# ffb_wheel.net
KiCad netlist of a schematic drawn in Altium Designer
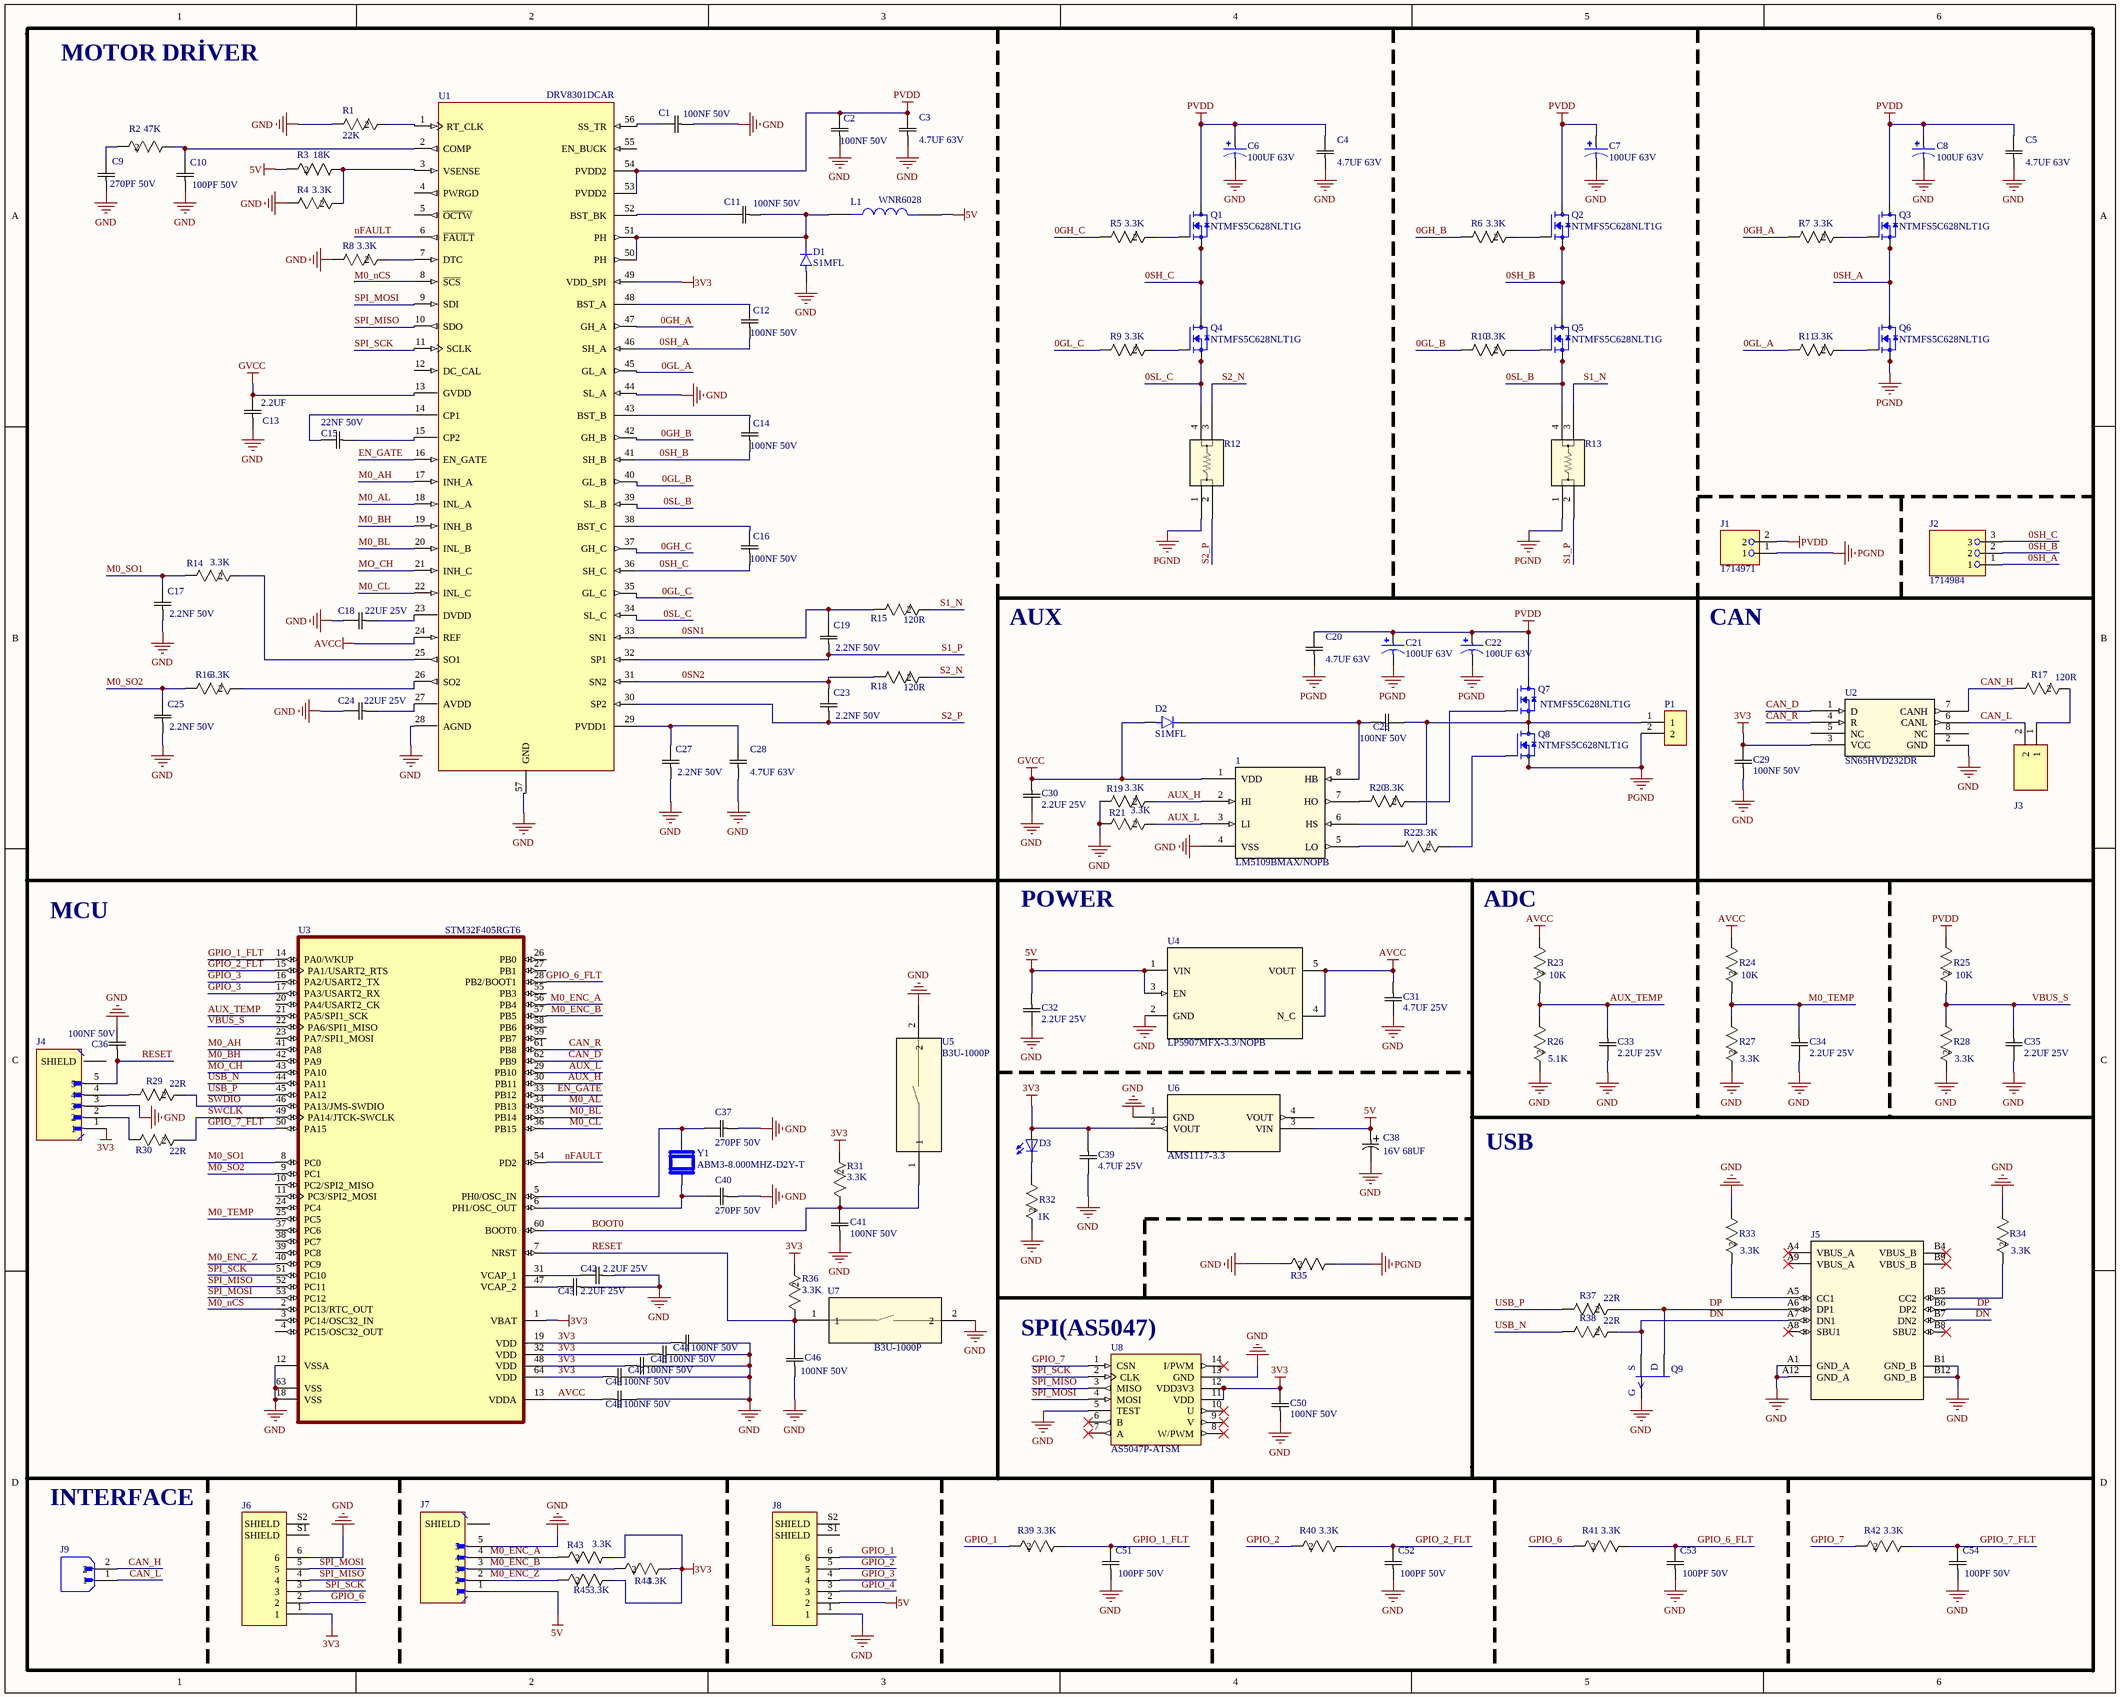
[diagram p0: ffb_wheel.SchDoc]

(export (version "E")
  (design (tool "Eeschema 10.0.6"))
  (components
    (comp (ref "1")
      (value "LM5109BMAX/NOPB")
      (footprint "M08A")
      (description "1-A, 100-V half bridge gate driver with 8-V UVLO and high noise immunity 8-SOIC -40 to 125")
      (fields (field (name "COPYRIGHT") "Copyright (C) 2025 Ultra Librarian. All rights reserved."))
      (libsource (lib "ffb_wheel") (part "LM5109BMAXNOPB"))
    )
    (comp (ref "C1")
      (value "100NF 50V")
      (footprint "CAP_0402_TDK")
      (description "No Description Available")
      (fields
        (field (name "MANUFACTURER_PART_NUMBER") "C0402X5R0J103K020BC")
        (field (name "COPYRIGHT") "Copyright (C) 2025 Ultra Librarian. All rights reserved.")
      )
      (libsource (lib "capacitor") (part "0402"))
    )
    (comp (ref "C2")
      (value "100NF 50V")
      (footprint "0603_AVX")
      (description "Description")
      (fields
        (field (name "MANUFACTURER_PART_NUMBER") "0603YC683KAT2A")
        (field (name "COPYRIGHT") "Copyright (C) 2025 Ultra Librarian. All rights reserved.")
      )
      (libsource (lib "capacitor") (part "0603"))
    )
    (comp (ref "C3")
      (value "4.7UF 63V")
      (footprint "CAP_1206_B_WAL")
      (description "Description")
      (fields
        (field (name "MANUFACTURER_PART_NUMBER") "1206B104J500CT")
        (field (name "COPYRIGHT") "Copyright (C) 2025 Ultra Librarian. All rights reserved.")
      )
      (libsource (lib "capacitor") (part "1206"))
    )
    (comp (ref "C4")
      (value "4.7UF 63V")
      (footprint "CAP_1206_B_WAL")
      (description "Description")
      (fields
        (field (name "MANUFACTURER_PART_NUMBER") "1206B104J500CT")
        (field (name "COPYRIGHT") "Copyright (C) 2025 Ultra Librarian. All rights reserved.")
      )
      (libsource (lib "capacitor") (part "1206"))
    )
    (comp (ref "C5")
      (value "4.7UF 63V")
      (footprint "CAP_1206_B_WAL")
      (description "Description")
      (fields
        (field (name "MANUFACTURER_PART_NUMBER") "1206B104J500CT")
        (field (name "COPYRIGHT") "Copyright (C) 2025 Ultra Librarian. All rights reserved.")
      )
      (libsource (lib "capacitor") (part "1206"))
    )
    (comp (ref "C6")
      (value "100UF 63V")
      (footprint "CAP_EEEFT1C102GP")
      (description "Cap Aluminum 1000uF 16V 20% (10 X 10.2mm) SMD Cylindrical 0.06 Ohm 1190mA 5000hr 105Â°C Emboss T/R")
      (fields (field (name "DIGI-KEY_PART_NUMBER") "PCE5115TR-ND") (field (name "MF") "Panasonic"))
      (libsource (lib "ffb_wheel") (part "EEEFT1C102GP"))
    )
    (comp (ref "C7")
      (value "100UF 63V")
      (footprint "CAP_EEEFT1C102GP")
      (description "Cap Aluminum 1000uF 16V 20% (10 X 10.2mm) SMD Cylindrical 0.06 Ohm 1190mA 5000hr 105Â°C Emboss T/R")
      (fields (field (name "DIGI-KEY_PART_NUMBER") "PCE5115TR-ND") (field (name "MF") "Panasonic"))
      (libsource (lib "ffb_wheel") (part "EEEFT1C102GP"))
    )
    (comp (ref "C8")
      (value "100UF 63V")
      (footprint "CAP_EEEFT1C102GP")
      (description "Cap Aluminum 1000uF 16V 20% (10 X 10.2mm) SMD Cylindrical 0.06 Ohm 1190mA 5000hr 105Â°C Emboss T/R")
      (fields (field (name "DIGI-KEY_PART_NUMBER") "PCE5115TR-ND") (field (name "MF") "Panasonic"))
      (libsource (lib "ffb_wheel") (part "EEEFT1C102GP"))
    )
    (comp (ref "C9")
      (value "270PF 50V")
      (footprint "CAP_0402_TDK")
      (description "No Description Available")
      (fields
        (field (name "MANUFACTURER_PART_NUMBER") "C0402X5R0J103K020BC")
        (field (name "COPYRIGHT") "Copyright (C) 2025 Ultra Librarian. All rights reserved.")
      )
      (libsource (lib "capacitor") (part "0402"))
    )
    (comp (ref "C10")
      (value "100PF 50V")
      (footprint "CAP_0402_TDK")
      (description "No Description Available")
      (fields
        (field (name "MANUFACTURER_PART_NUMBER") "C0402X5R0J103K020BC")
        (field (name "COPYRIGHT") "Copyright (C) 2025 Ultra Librarian. All rights reserved.")
      )
      (libsource (lib "capacitor") (part "0402"))
    )
    (comp (ref "C11")
      (value "100NF 50V")
      (footprint "0603_AVX")
      (description "Description")
      (fields
        (field (name "MANUFACTURER_PART_NUMBER") "0603YC683KAT2A")
        (field (name "COPYRIGHT") "Copyright (C) 2025 Ultra Librarian. All rights reserved.")
      )
      (libsource (lib "capacitor") (part "0603"))
    )
    (comp (ref "C12")
      (value "100NF 50V")
      (footprint "0603_AVX")
      (description "Description")
      (fields
        (field (name "MANUFACTURER_PART_NUMBER") "0603YC683KAT2A")
        (field (name "COPYRIGHT") "Copyright (C) 2025 Ultra Librarian. All rights reserved.")
      )
      (libsource (lib "capacitor") (part "0603"))
    )
    (comp (ref "C13")
      (value "2.2UF")
      (footprint "0805_AVX")
      (description "Description")
      (fields
        (field (name "MANUFACTURER_PART_NUMBER") "08051C473KAT2A")
        (field (name "COPYRIGHT") "Copyright (C) 2025 Ultra Librarian. All rights reserved.")
      )
      (libsource (lib "capacitor") (part "0805"))
    )
    (comp (ref "C14")
      (value "100NF 50V")
      (footprint "0603_AVX")
      (description "Description")
      (fields
        (field (name "MANUFACTURER_PART_NUMBER") "0603YC683KAT2A")
        (field (name "COPYRIGHT") "Copyright (C) 2025 Ultra Librarian. All rights reserved.")
      )
      (libsource (lib "capacitor") (part "0603"))
    )
    (comp (ref "C15")
      (value "22NF 50V")
      (footprint "CAP_0402_TDK")
      (description "No Description Available")
      (fields
        (field (name "MANUFACTURER_PART_NUMBER") "C0402X5R0J103K020BC")
        (field (name "COPYRIGHT") "Copyright (C) 2025 Ultra Librarian. All rights reserved.")
      )
      (libsource (lib "capacitor") (part "0402"))
    )
    (comp (ref "C16")
      (value "100NF 50V")
      (footprint "0603_AVX")
      (description "Description")
      (fields
        (field (name "MANUFACTURER_PART_NUMBER") "0603YC683KAT2A")
        (field (name "COPYRIGHT") "Copyright (C) 2025 Ultra Librarian. All rights reserved.")
      )
      (libsource (lib "capacitor") (part "0603"))
    )
    (comp (ref "C17")
      (value "2.2NF 50V")
      (footprint "CAP_0402_TDK")
      (description "No Description Available")
      (fields
        (field (name "MANUFACTURER_PART_NUMBER") "C0402X5R0J103K020BC")
        (field (name "COPYRIGHT") "Copyright (C) 2025 Ultra Librarian. All rights reserved.")
      )
      (libsource (lib "capacitor") (part "0402"))
    )
    (comp (ref "C18")
      (value "22UF 25V")
      (footprint "0805_AVX")
      (description "Description")
      (fields
        (field (name "MANUFACTURER_PART_NUMBER") "08051C473KAT2A")
        (field (name "COPYRIGHT") "Copyright (C) 2025 Ultra Librarian. All rights reserved.")
      )
      (libsource (lib "capacitor") (part "0805"))
    )
    (comp (ref "C19")
      (value "2.2NF 50V")
      (footprint "CAP_0402_TDK")
      (description "No Description Available")
      (fields
        (field (name "MANUFACTURER_PART_NUMBER") "C0402X5R0J103K020BC")
        (field (name "COPYRIGHT") "Copyright (C) 2025 Ultra Librarian. All rights reserved.")
      )
      (libsource (lib "capacitor") (part "0402"))
    )
    (comp (ref "C20")
      (value "4.7UF 63V")
      (footprint "CAP_1206_B_WAL")
      (description "Description")
      (fields
        (field (name "MANUFACTURER_PART_NUMBER") "1206B104J500CT")
        (field (name "COPYRIGHT") "Copyright (C) 2025 Ultra Librarian. All rights reserved.")
      )
      (libsource (lib "capacitor") (part "1206"))
    )
    (comp (ref "C21")
      (value "100UF 63V")
      (footprint "CAP_EEEFT1C102GP")
      (description "Cap Aluminum 1000uF 16V 20% (10 X 10.2mm) SMD Cylindrical 0.06 Ohm 1190mA 5000hr 105Â°C Emboss T/R")
      (fields (field (name "DIGI-KEY_PART_NUMBER") "PCE5115TR-ND") (field (name "MF") "Panasonic"))
      (libsource (lib "ffb_wheel") (part "EEEFT1C102GP"))
    )
    (comp (ref "C22")
      (value "100UF 63V")
      (footprint "CAP_EEEFT1C102GP")
      (description "Cap Aluminum 1000uF 16V 20% (10 X 10.2mm) SMD Cylindrical 0.06 Ohm 1190mA 5000hr 105Â°C Emboss T/R")
      (fields (field (name "DIGI-KEY_PART_NUMBER") "PCE5115TR-ND") (field (name "MF") "Panasonic"))
      (libsource (lib "ffb_wheel") (part "EEEFT1C102GP"))
    )
    (comp (ref "C23")
      (value "2.2NF 50V")
      (footprint "CAP_0402_TDK")
      (description "No Description Available")
      (fields
        (field (name "MANUFACTURER_PART_NUMBER") "C0402X5R0J103K020BC")
        (field (name "COPYRIGHT") "Copyright (C) 2025 Ultra Librarian. All rights reserved.")
      )
      (libsource (lib "capacitor") (part "0402"))
    )
    (comp (ref "C24")
      (value "22UF 25V")
      (footprint "0805_AVX")
      (description "Description")
      (fields
        (field (name "MANUFACTURER_PART_NUMBER") "08051C473KAT2A")
        (field (name "COPYRIGHT") "Copyright (C) 2025 Ultra Librarian. All rights reserved.")
      )
      (libsource (lib "capacitor") (part "0805"))
    )
    (comp (ref "C25")
      (value "2.2NF 50V")
      (footprint "CAP_0402_TDK")
      (description "No Description Available")
      (fields
        (field (name "MANUFACTURER_PART_NUMBER") "C0402X5R0J103K020BC")
        (field (name "COPYRIGHT") "Copyright (C) 2025 Ultra Librarian. All rights reserved.")
      )
      (libsource (lib "capacitor") (part "0402"))
    )
    (comp (ref "C26")
      (value "100NF 50V")
      (footprint "0603_AVX")
      (description "Description")
      (fields
        (field (name "MANUFACTURER_PART_NUMBER") "0603YC683KAT2A")
        (field (name "COPYRIGHT") "Copyright (C) 2025 Ultra Librarian. All rights reserved.")
      )
      (libsource (lib "capacitor") (part "0603"))
    )
    (comp (ref "C27")
      (value "2.2NF 50V")
      (footprint "CAP_0402_TDK")
      (description "No Description Available")
      (fields
        (field (name "MANUFACTURER_PART_NUMBER") "C0402X5R0J103K020BC")
        (field (name "COPYRIGHT") "Copyright (C) 2025 Ultra Librarian. All rights reserved.")
      )
      (libsource (lib "capacitor") (part "0402"))
    )
    (comp (ref "C28")
      (value "4.7UF 63V")
      (footprint "CAP_1206_B_WAL")
      (description "Description")
      (fields
        (field (name "MANUFACTURER_PART_NUMBER") "1206B104J500CT")
        (field (name "COPYRIGHT") "Copyright (C) 2025 Ultra Librarian. All rights reserved.")
      )
      (libsource (lib "capacitor") (part "1206"))
    )
    (comp (ref "C29")
      (value "100NF 50V")
      (footprint "0603_AVX")
      (description "Description")
      (fields
        (field (name "MANUFACTURER_PART_NUMBER") "0603YC683KAT2A")
        (field (name "COPYRIGHT") "Copyright (C) 2025 Ultra Librarian. All rights reserved.")
      )
      (libsource (lib "capacitor") (part "0603"))
    )
    (comp (ref "C30")
      (value "2.2UF 25V")
      (footprint "0805_AVX")
      (description "Description")
      (fields
        (field (name "MANUFACTURER_PART_NUMBER") "08051C473KAT2A")
        (field (name "COPYRIGHT") "Copyright (C) 2025 Ultra Librarian. All rights reserved.")
      )
      (libsource (lib "capacitor") (part "0805"))
    )
    (comp (ref "C31")
      (value "4.7UF 25V")
      (footprint "0805_AVX")
      (description "Description")
      (fields
        (field (name "MANUFACTURER_PART_NUMBER") "08051C473KAT2A")
        (field (name "COPYRIGHT") "Copyright (C) 2025 Ultra Librarian. All rights reserved.")
      )
      (libsource (lib "capacitor") (part "0805"))
    )
    (comp (ref "C32")
      (value "2.2UF 25V")
      (footprint "0805_AVX")
      (description "Description")
      (fields
        (field (name "MANUFACTURER_PART_NUMBER") "08051C473KAT2A")
        (field (name "COPYRIGHT") "Copyright (C) 2025 Ultra Librarian. All rights reserved.")
      )
      (libsource (lib "capacitor") (part "0805"))
    )
    (comp (ref "C33")
      (value "2.2UF 25V")
      (footprint "0805_AVX")
      (description "Description")
      (fields
        (field (name "MANUFACTURER_PART_NUMBER") "08051C473KAT2A")
        (field (name "COPYRIGHT") "Copyright (C) 2025 Ultra Librarian. All rights reserved.")
      )
      (libsource (lib "capacitor") (part "0805"))
    )
    (comp (ref "C34")
      (value "2.2UF 25V")
      (footprint "0805_AVX")
      (description "Description")
      (fields
        (field (name "MANUFACTURER_PART_NUMBER") "08051C473KAT2A")
        (field (name "COPYRIGHT") "Copyright (C) 2025 Ultra Librarian. All rights reserved.")
      )
      (libsource (lib "capacitor") (part "0805"))
    )
    (comp (ref "C35")
      (value "2.2UF 25V")
      (footprint "0805_AVX")
      (description "Description")
      (fields
        (field (name "MANUFACTURER_PART_NUMBER") "08051C473KAT2A")
        (field (name "COPYRIGHT") "Copyright (C) 2025 Ultra Librarian. All rights reserved.")
      )
      (libsource (lib "capacitor") (part "0805"))
    )
    (comp (ref "C36")
      (value "100NF 50V")
      (footprint "0603_AVX")
      (description "Description")
      (fields
        (field (name "MANUFACTURER_PART_NUMBER") "0603YC683KAT2A")
        (field (name "COPYRIGHT") "Copyright (C) 2025 Ultra Librarian. All rights reserved.")
      )
      (libsource (lib "capacitor") (part "0603"))
    )
    (comp (ref "C37")
      (value "270PF 50V")
      (footprint "CAP_0402_TDK")
      (description "No Description Available")
      (fields
        (field (name "MANUFACTURER_PART_NUMBER") "C0402X5R0J103K020BC")
        (field (name "COPYRIGHT") "Copyright (C) 2025 Ultra Librarian. All rights reserved.")
      )
      (libsource (lib "capacitor") (part "0402"))
    )
    (comp (ref "C38")
      (value "16V 68UF")
      (footprint "TAJB_AVX")
      (description "Cap Tant Solid 47uF 6.3V B CASE 10% (3.5 X 2.8 X 1.9mm)")
      (fields
        (field (name "MANUFACTURER_PART_NUMBER") "TAJB476K006RNJ")
        (field (name "COPYRIGHT") "Copyright (C) 2025 Ultra Librarian. All rights reserved.")
      )
      (libsource (lib "capacitor") (part "(3.5 X 2.8 X 1.9mm)"))
    )
    (comp (ref "C39")
      (value "4.7UF 25V")
      (footprint "0805_AVX")
      (description "Description")
      (fields
        (field (name "MANUFACTURER_PART_NUMBER") "08051C473KAT2A")
        (field (name "COPYRIGHT") "Copyright (C) 2025 Ultra Librarian. All rights reserved.")
      )
      (libsource (lib "capacitor") (part "0805"))
    )
    (comp (ref "C40")
      (value "270PF 50V")
      (footprint "CAP_0402_TDK")
      (description "No Description Available")
      (fields
        (field (name "MANUFACTURER_PART_NUMBER") "C0402X5R0J103K020BC")
        (field (name "COPYRIGHT") "Copyright (C) 2025 Ultra Librarian. All rights reserved.")
      )
      (libsource (lib "capacitor") (part "0402"))
    )
    (comp (ref "C41")
      (value "100NF 50V")
      (footprint "0603_AVX")
      (description "Description")
      (fields
        (field (name "MANUFACTURER_PART_NUMBER") "0603YC683KAT2A")
        (field (name "COPYRIGHT") "Copyright (C) 2025 Ultra Librarian. All rights reserved.")
      )
      (libsource (lib "capacitor") (part "0603"))
    )
    (comp (ref "C42")
      (value "2.2UF 25V")
      (footprint "0805_AVX")
      (description "Description")
      (fields
        (field (name "MANUFACTURER_PART_NUMBER") "08051C473KAT2A")
        (field (name "COPYRIGHT") "Copyright (C) 2025 Ultra Librarian. All rights reserved.")
      )
      (libsource (lib "capacitor") (part "0805"))
    )
    (comp (ref "C43")
      (value "2.2UF 25V")
      (footprint "0805_AVX")
      (description "Description")
      (fields
        (field (name "MANUFACTURER_PART_NUMBER") "08051C473KAT2A")
        (field (name "COPYRIGHT") "Copyright (C) 2025 Ultra Librarian. All rights reserved.")
      )
      (libsource (lib "capacitor") (part "0805"))
    )
    (comp (ref "C44")
      (value "100NF 50V")
      (footprint "0603_AVX")
      (description "Description")
      (fields
        (field (name "MANUFACTURER_PART_NUMBER") "0603YC683KAT2A")
        (field (name "COPYRIGHT") "Copyright (C) 2025 Ultra Librarian. All rights reserved.")
      )
      (libsource (lib "capacitor") (part "0603"))
    )
    (comp (ref "C45")
      (value "100NF 50V")
      (footprint "0603_AVX")
      (description "Description")
      (fields
        (field (name "MANUFACTURER_PART_NUMBER") "0603YC683KAT2A")
        (field (name "COPYRIGHT") "Copyright (C) 2025 Ultra Librarian. All rights reserved.")
      )
      (libsource (lib "capacitor") (part "0603"))
    )
    (comp (ref "C46")
      (value "100NF 50V")
      (footprint "0603_AVX")
      (description "Description")
      (fields
        (field (name "MANUFACTURER_PART_NUMBER") "0603YC683KAT2A")
        (field (name "COPYRIGHT") "Copyright (C) 2025 Ultra Librarian. All rights reserved.")
      )
      (libsource (lib "capacitor") (part "0603"))
    )
    (comp (ref "C47")
      (value "100NF 50V")
      (footprint "0603_AVX")
      (description "Description")
      (fields
        (field (name "MANUFACTURER_PART_NUMBER") "0603YC683KAT2A")
        (field (name "COPYRIGHT") "Copyright (C) 2025 Ultra Librarian. All rights reserved.")
      )
      (libsource (lib "capacitor") (part "0603"))
    )
    (comp (ref "C48")
      (value "100NF 50V")
      (footprint "0603_AVX")
      (description "Description")
      (fields
        (field (name "MANUFACTURER_PART_NUMBER") "0603YC683KAT2A")
        (field (name "COPYRIGHT") "Copyright (C) 2025 Ultra Librarian. All rights reserved.")
      )
      (libsource (lib "capacitor") (part "0603"))
    )
    (comp (ref "C49")
      (value "100NF 50V")
      (footprint "0603_AVX")
      (description "Description")
      (fields
        (field (name "MANUFACTURER_PART_NUMBER") "0603YC683KAT2A")
        (field (name "COPYRIGHT") "Copyright (C) 2025 Ultra Librarian. All rights reserved.")
      )
      (libsource (lib "capacitor") (part "0603"))
    )
    (comp (ref "C50")
      (value "100NF 50V")
      (footprint "0603_AVX")
      (description "Description")
      (fields
        (field (name "MANUFACTURER_PART_NUMBER") "0603YC683KAT2A")
        (field (name "COPYRIGHT") "Copyright (C) 2025 Ultra Librarian. All rights reserved.")
      )
      (libsource (lib "capacitor") (part "0603"))
    )
    (comp (ref "C51")
      (value "100PF 50V")
      (footprint "CAP_0402_TDK")
      (description "No Description Available")
      (fields
        (field (name "MANUFACTURER_PART_NUMBER") "C0402X5R0J103K020BC")
        (field (name "COPYRIGHT") "Copyright (C) 2025 Ultra Librarian. All rights reserved.")
      )
      (libsource (lib "capacitor") (part "0402"))
    )
    (comp (ref "C52")
      (value "100PF 50V")
      (footprint "CAP_0402_TDK")
      (description "No Description Available")
      (fields
        (field (name "MANUFACTURER_PART_NUMBER") "C0402X5R0J103K020BC")
        (field (name "COPYRIGHT") "Copyright (C) 2025 Ultra Librarian. All rights reserved.")
      )
      (libsource (lib "capacitor") (part "0402"))
    )
    (comp (ref "C53")
      (value "100PF 50V")
      (footprint "CAP_0402_TDK")
      (description "No Description Available")
      (fields
        (field (name "MANUFACTURER_PART_NUMBER") "C0402X5R0J103K020BC")
        (field (name "COPYRIGHT") "Copyright (C) 2025 Ultra Librarian. All rights reserved.")
      )
      (libsource (lib "capacitor") (part "0402"))
    )
    (comp (ref "C54")
      (value "100PF 50V")
      (footprint "CAP_0402_TDK")
      (description "No Description Available")
      (fields
        (field (name "MANUFACTURER_PART_NUMBER") "C0402X5R0J103K020BC")
        (field (name "COPYRIGHT") "Copyright (C) 2025 Ultra Librarian. All rights reserved.")
      )
      (libsource (lib "capacitor") (part "0402"))
    )
    (comp (ref "D1")
      (value "S1MFL")
      (footprint "SODFL3617X108N")
      (description "Diode Standard 1000 V 1A Surface Mount SOD-123F")
      (fields (field (name "MF") "ON Semiconductor"))
      (libsource (lib "ffb_wheel") (part "S1MFL"))
    )
    (comp (ref "D2")
      (value "S1MFL")
      (footprint "SODFL3617X108N")
      (description "Diode Standard 1000 V 1A Surface Mount SOD-123F")
      (fields (field (name "MF") "ON Semiconductor"))
      (libsource (lib "ffb_wheel") (part "S1MFL"))
    )
    (comp (ref "D3")
      (value "LTST-C170TBKT")
      (footprint "DIOC200X125X110")
      (description "Blue 470nm LED Indication - Discrete 3.3V 0805 (2012 Metric)")
      (fields (field (name "MF") "Lite-On Electronics"))
      (libsource (lib "batterie") (part "LTST-C170TBKT"))
    )
    (comp (ref "J1")
      (value "1714971")
      (footprint "PHOENIX_1714971")
      (libsource (lib "ffb_wheel") (part "1714971"))
    )
    (comp (ref "J2")
      (value "1714984")
      (footprint "PHOENIX_1714984")
      (fields (field (name "MF") "Phoenix Contact"))
      (libsource (lib "ffb_wheel") (part "1714984"))
    )
    (comp (ref "J3")
      (value "3-644456-2")
      (footprint "TE_3-644456-2")
      (description "HEADER ASSEMBLY, NARROW, MTA-100, 2 POSITION, STRAIGHT ¦ TE Connectivity 3-644456-2")
      (fields (field (name "MF") "TE Connectivity"))
      (libsource (lib "ffb_wheel") (part "3-644456-2"))
    )
    (comp (ref "J4")
      (value "BM05B-GHS-TBT(LF)(SN)(N)")
      (footprint "JST_BM05B-GHS-TBT(LF)(SN)(N)")
      (description "Connector Header Surface Mount 5 position 0.049 (1.25mm)")
      (fields (field (name "MF") "JST Sales"))
      (libsource (lib "ffb_wheel") (part "BM05B-GHS-TBT(LF)(SN)(N)"))
    )
    (comp (ref "J5")
      (value "USB4145-03-0230-C")
      (footprint "CONN_USB4145-03-0230-C_GCT")
      (description "Description")
      (fields (field (name "COPYRIGHT") "Copyright (C) 2025 Ultra Librarian. All rights reserved."))
      (libsource (lib "ffb_wheel") (part "USB4145-03-0230-C"))
    )
    (comp (ref "J6")
      (value "BM06B-GHS-TBT(LF)(SN)(N)")
      (footprint "JST_BM06B-GHS-TBT(LF)(SN)(N)")
      (description "Connector Header Surface Mount 6 position 0.049 (1.25mm)")
      (fields (field (name "MF") "JST Sales"))
      (libsource (lib "ffb_wheel") (part "BM06B-GHS-TBT(LF)(SN)(N)"))
    )
    (comp (ref "J7")
      (value "BM05B-GHS-TBT(LF)(SN)(N)")
      (footprint "JST_BM05B-GHS-TBT(LF)(SN)(N)")
      (description "Connector Header Surface Mount 5 position 0.049 (1.25mm)")
      (fields (field (name "MF") "JST Sales"))
      (libsource (lib "ffb_wheel") (part "BM05B-GHS-TBT(LF)(SN)(N)"))
    )
    (comp (ref "J8")
      (value "BM06B-GHS-TBT(LF)(SN)(N)")
      (footprint "JST_BM06B-GHS-TBT(LF)(SN)(N)")
      (description "Connector Header Surface Mount 6 position 0.049 (1.25mm)")
      (fields (field (name "MF") "JST Sales"))
      (libsource (lib "ffb_wheel") (part "BM06B-GHS-TBT(LF)(SN)(N)"))
    )
    (comp (ref "J9")
      (value "BM02B-GHS-TBT(LF)(SN)")
      (footprint "JST_BM02B-GHS-TBT(LF)(SN)")
      (description "Connector Header Surface Mount 2 position 0.049 (1.25mm)")
      (fields (field (name "MF") "JST Sales") (field (name "MP") "BM02B-GHS-TBT (LF)(SN)"))
      (libsource (lib "ffb_wheel") (part "BM02B-GHS-TBT(LF)(SN)"))
    )
    (comp (ref "L1")
      (value "WNR6028")
      (footprint "IND_NR6028T4R7M")
      (description "4.7 ÂµH Shielded Drum Core, Wirewound Inductor 3 A 40.3mOhm Max Nonstandard")
      (fields (field (name "MF") "Taiyo Yuden") (field (name "MP") "NR6028T4R7M"))
      (libsource (lib "ffb_wheel") (part "NR6028T4R7M"))
    )
    (comp (ref "P1")
      (value "282837-2")
      (footprint "TE_282837-2")
      (fields (field (name "MF") "TE Connectivity"))
      (libsource (lib "ffb_wheel") (part "282837-2"))
    )
    (comp (ref "Q1")
      (value "NTMFS5C628NLT1G")
      (footprint "TRANS_NTMFS5C628NLT1G")
      (description "N-Channel 60 V 28A (Ta), 150A (Tc) 3.7W (Ta), 110W (Tc) Surface Mount 5-DFN (5x6) (8-SOFL)")
      (fields (field (name "MF") "ON Semiconductor"))
      (libsource (lib "ffb_wheel") (part "NTMFS5C628NLT1G"))
    )
    (comp (ref "Q2")
      (value "NTMFS5C628NLT1G")
      (footprint "TRANS_NTMFS5C628NLT1G")
      (description "N-Channel 60 V 28A (Ta), 150A (Tc) 3.7W (Ta), 110W (Tc) Surface Mount 5-DFN (5x6) (8-SOFL)")
      (fields (field (name "MF") "ON Semiconductor"))
      (libsource (lib "ffb_wheel") (part "NTMFS5C628NLT1G"))
    )
    (comp (ref "Q3")
      (value "NTMFS5C628NLT1G")
      (footprint "TRANS_NTMFS5C628NLT1G")
      (description "N-Channel 60 V 28A (Ta), 150A (Tc) 3.7W (Ta), 110W (Tc) Surface Mount 5-DFN (5x6) (8-SOFL)")
      (fields (field (name "MF") "ON Semiconductor"))
      (libsource (lib "ffb_wheel") (part "NTMFS5C628NLT1G"))
    )
    (comp (ref "Q4")
      (value "NTMFS5C628NLT1G")
      (footprint "TRANS_NTMFS5C628NLT1G")
      (description "N-Channel 60 V 28A (Ta), 150A (Tc) 3.7W (Ta), 110W (Tc) Surface Mount 5-DFN (5x6) (8-SOFL)")
      (fields (field (name "MF") "ON Semiconductor"))
      (libsource (lib "ffb_wheel") (part "NTMFS5C628NLT1G"))
    )
    (comp (ref "Q5")
      (value "NTMFS5C628NLT1G")
      (footprint "TRANS_NTMFS5C628NLT1G")
      (description "N-Channel 60 V 28A (Ta), 150A (Tc) 3.7W (Ta), 110W (Tc) Surface Mount 5-DFN (5x6) (8-SOFL)")
      (fields (field (name "MF") "ON Semiconductor"))
      (libsource (lib "ffb_wheel") (part "NTMFS5C628NLT1G"))
    )
    (comp (ref "Q6")
      (value "NTMFS5C628NLT1G")
      (footprint "TRANS_NTMFS5C628NLT1G")
      (description "N-Channel 60 V 28A (Ta), 150A (Tc) 3.7W (Ta), 110W (Tc) Surface Mount 5-DFN (5x6) (8-SOFL)")
      (fields (field (name "MF") "ON Semiconductor"))
      (libsource (lib "ffb_wheel") (part "NTMFS5C628NLT1G"))
    )
    (comp (ref "Q7")
      (value "NTMFS5C628NLT1G")
      (footprint "TRANS_NTMFS5C628NLT1G")
      (description "N-Channel 60 V 28A (Ta), 150A (Tc) 3.7W (Ta), 110W (Tc) Surface Mount 5-DFN (5x6) (8-SOFL)")
      (fields (field (name "MF") "ON Semiconductor"))
      (libsource (lib "ffb_wheel") (part "NTMFS5C628NLT1G"))
    )
    (comp (ref "Q8")
      (value "NTMFS5C628NLT1G")
      (footprint "TRANS_NTMFS5C628NLT1G")
      (description "N-Channel 60 V 28A (Ta), 150A (Tc) 3.7W (Ta), 110W (Tc) Surface Mount 5-DFN (5x6) (8-SOFL)")
      (fields (field (name "MF") "ON Semiconductor"))
      (libsource (lib "ffb_wheel") (part "NTMFS5C628NLT1G"))
    )
    (comp (ref "Q9")
      (value "SST176-SOT-23_3L")
      (footprint "SOT96P237X122-3N")
      (description "P-CHANNEL, SINGLE, JFET SWITCH")
      (fields (field (name "MF") "Linear Systems") (field (name "MP") "SST176-SOT-23 3L"))
      (libsource (lib "ffb_wheel") (part "SST176-SOT-23_3L"))
    )
    (comp (ref "R1")
      (value "22K")
      (footprint "RC0603N_PAN")
      (description "No Description Available")
      (fields
        (field (name "MANUFACTURER_PART_NUMBER") "ERJ-3GEYJ6R8V")
        (field (name "COPYRIGHT") "Copyright (C) 2025 Ultra Librarian. All rights reserved.")
      )
      (libsource (lib "resistor") (part "0603"))
    )
    (comp (ref "R2")
      (value "47K")
      (footprint "RC0603N_PAN")
      (description "No Description Available")
      (fields
        (field (name "MANUFACTURER_PART_NUMBER") "ERJ-3GEYJ6R8V")
        (field (name "COPYRIGHT") "Copyright (C) 2025 Ultra Librarian. All rights reserved.")
      )
      (libsource (lib "resistor") (part "0603"))
    )
    (comp (ref "R3")
      (value "18K")
      (footprint "RC0603N_PAN")
      (description "No Description Available")
      (fields
        (field (name "MANUFACTURER_PART_NUMBER") "ERJ-3GEYJ6R8V")
        (field (name "COPYRIGHT") "Copyright (C) 2025 Ultra Librarian. All rights reserved.")
      )
      (libsource (lib "resistor") (part "0603"))
    )
    (comp (ref "R4")
      (value "3.3K")
      (footprint "RC0603N_PAN")
      (description "No Description Available")
      (fields
        (field (name "MANUFACTURER_PART_NUMBER") "ERJ-3GEYJ6R8V")
        (field (name "COPYRIGHT") "Copyright (C) 2025 Ultra Librarian. All rights reserved.")
      )
      (libsource (lib "resistor") (part "0603"))
    )
    (comp (ref "R5")
      (value "3.3K")
      (footprint "RC0603N_PAN")
      (description "No Description Available")
      (fields
        (field (name "MANUFACTURER_PART_NUMBER") "ERJ-3GEYJ6R8V")
        (field (name "COPYRIGHT") "Copyright (C) 2025 Ultra Librarian. All rights reserved.")
      )
      (libsource (lib "resistor") (part "0603"))
    )
    (comp (ref "R6")
      (value "3.3K")
      (footprint "RC0603N_PAN")
      (description "No Description Available")
      (fields
        (field (name "MANUFACTURER_PART_NUMBER") "ERJ-3GEYJ6R8V")
        (field (name "COPYRIGHT") "Copyright (C) 2025 Ultra Librarian. All rights reserved.")
      )
      (libsource (lib "resistor") (part "0603"))
    )
    (comp (ref "R7")
      (value "3.3K")
      (footprint "RC0603N_PAN")
      (description "No Description Available")
      (fields
        (field (name "MANUFACTURER_PART_NUMBER") "ERJ-3GEYJ6R8V")
        (field (name "COPYRIGHT") "Copyright (C) 2025 Ultra Librarian. All rights reserved.")
      )
      (libsource (lib "resistor") (part "0603"))
    )
    (comp (ref "R8")
      (value "3.3K")
      (footprint "RC0603N_PAN")
      (description "No Description Available")
      (fields
        (field (name "MANUFACTURER_PART_NUMBER") "ERJ-3GEYJ6R8V")
        (field (name "COPYRIGHT") "Copyright (C) 2025 Ultra Librarian. All rights reserved.")
      )
      (libsource (lib "resistor") (part "0603"))
    )
    (comp (ref "R9")
      (value "3.3K")
      (footprint "RC0603N_PAN")
      (description "No Description Available")
      (fields
        (field (name "MANUFACTURER_PART_NUMBER") "ERJ-3GEYJ6R8V")
        (field (name "COPYRIGHT") "Copyright (C) 2025 Ultra Librarian. All rights reserved.")
      )
      (libsource (lib "resistor") (part "0603"))
    )
    (comp (ref "R10")
      (value "3.3K")
      (footprint "RC0603N_PAN")
      (description "No Description Available")
      (fields
        (field (name "MANUFACTURER_PART_NUMBER") "ERJ-3GEYJ6R8V")
        (field (name "COPYRIGHT") "Copyright (C) 2025 Ultra Librarian. All rights reserved.")
      )
      (libsource (lib "resistor") (part "0603"))
    )
    (comp (ref "R11")
      (value "3.3K")
      (footprint "RC0603N_PAN")
      (description "No Description Available")
      (fields
        (field (name "MANUFACTURER_PART_NUMBER") "ERJ-3GEYJ6R8V")
        (field (name "COPYRIGHT") "Copyright (C) 2025 Ultra Librarian. All rights reserved.")
      )
      (libsource (lib "resistor") (part "0603"))
    )
    (comp (ref "R12")
      (value "WSK2512R0100DEA")
      (footprint "WSK2512_0.005-0.2_VIS")
      (description "WSK-2512 .01 .5% EA e3")
      (fields (field (name "COPYRIGHT") "Copyright (C) 2025 Ultra Librarian. All rights reserved."))
      (libsource (lib "ffb_wheel") (part "WSK2512R0100DEA"))
    )
    (comp (ref "R13")
      (value "WSK2512R0100DEA")
      (footprint "WSK2512_0.005-0.2_VIS")
      (description "WSK-2512 .01 .5% EA e3")
      (fields (field (name "COPYRIGHT") "Copyright (C) 2025 Ultra Librarian. All rights reserved."))
      (libsource (lib "ffb_wheel") (part "WSK2512R0100DEA"))
    )
    (comp (ref "R14")
      (value "3.3K")
      (footprint "RC0603N_PAN")
      (description "No Description Available")
      (fields
        (field (name "MANUFACTURER_PART_NUMBER") "ERJ-3GEYJ6R8V")
        (field (name "COPYRIGHT") "Copyright (C) 2025 Ultra Librarian. All rights reserved.")
      )
      (libsource (lib "resistor") (part "0603"))
    )
    (comp (ref "R15")
      (value "120R")
      (footprint "RC0603N_PAN")
      (description "No Description Available")
      (fields
        (field (name "MANUFACTURER_PART_NUMBER") "ERJ-3GEYJ6R8V")
        (field (name "COPYRIGHT") "Copyright (C) 2025 Ultra Librarian. All rights reserved.")
      )
      (libsource (lib "resistor") (part "0603"))
    )
    (comp (ref "R16")
      (value "3.3K")
      (footprint "RC0603N_PAN")
      (description "No Description Available")
      (fields
        (field (name "MANUFACTURER_PART_NUMBER") "ERJ-3GEYJ6R8V")
        (field (name "COPYRIGHT") "Copyright (C) 2025 Ultra Librarian. All rights reserved.")
      )
      (libsource (lib "resistor") (part "0603"))
    )
    (comp (ref "R17")
      (value "120R")
      (footprint "RC0603N_PAN")
      (description "No Description Available")
      (fields
        (field (name "MANUFACTURER_PART_NUMBER") "ERJ-3GEYJ6R8V")
        (field (name "COPYRIGHT") "Copyright (C) 2025 Ultra Librarian. All rights reserved.")
      )
      (libsource (lib "resistor") (part "0603"))
    )
    (comp (ref "R18")
      (value "120R")
      (footprint "RC0603N_PAN")
      (description "No Description Available")
      (fields
        (field (name "MANUFACTURER_PART_NUMBER") "ERJ-3GEYJ6R8V")
        (field (name "COPYRIGHT") "Copyright (C) 2025 Ultra Librarian. All rights reserved.")
      )
      (libsource (lib "resistor") (part "0603"))
    )
    (comp (ref "R19")
      (value "3.3K")
      (footprint "RC0603N_PAN")
      (description "No Description Available")
      (fields
        (field (name "MANUFACTURER_PART_NUMBER") "ERJ-3GEYJ6R8V")
        (field (name "COPYRIGHT") "Copyright (C) 2025 Ultra Librarian. All rights reserved.")
      )
      (libsource (lib "resistor") (part "0603"))
    )
    (comp (ref "R20")
      (value "3.3K")
      (footprint "RC0603N_PAN")
      (description "No Description Available")
      (fields
        (field (name "MANUFACTURER_PART_NUMBER") "ERJ-3GEYJ6R8V")
        (field (name "COPYRIGHT") "Copyright (C) 2025 Ultra Librarian. All rights reserved.")
      )
      (libsource (lib "resistor") (part "0603"))
    )
    (comp (ref "R21")
      (value "3.3K")
      (footprint "RC0603N_PAN")
      (description "No Description Available")
      (fields
        (field (name "MANUFACTURER_PART_NUMBER") "ERJ-3GEYJ6R8V")
        (field (name "COPYRIGHT") "Copyright (C) 2025 Ultra Librarian. All rights reserved.")
      )
      (libsource (lib "resistor") (part "0603"))
    )
    (comp (ref "R22")
      (value "3.3K")
      (footprint "RC0603N_PAN")
      (description "No Description Available")
      (fields
        (field (name "MANUFACTURER_PART_NUMBER") "ERJ-3GEYJ6R8V")
        (field (name "COPYRIGHT") "Copyright (C) 2025 Ultra Librarian. All rights reserved.")
      )
      (libsource (lib "resistor") (part "0603"))
    )
    (comp (ref "R23")
      (value "10K")
      (footprint "RC0402N_PAN")
      (description "No Description Available")
      (fields
        (field (name "MANUFACTURER_PART_NUMBER") "ERJ-2GEJ433X")
        (field (name "COPYRIGHT") "Copyright (C) 2025 Ultra Librarian. All rights reserved.")
      )
      (libsource (lib "resistor") (part "0402"))
    )
    (comp (ref "R24")
      (value "10K")
      (footprint "RC0402N_PAN")
      (description "No Description Available")
      (fields
        (field (name "MANUFACTURER_PART_NUMBER") "ERJ-2GEJ433X")
        (field (name "COPYRIGHT") "Copyright (C) 2025 Ultra Librarian. All rights reserved.")
      )
      (libsource (lib "resistor") (part "0402"))
    )
    (comp (ref "R25")
      (value "10K")
      (footprint "RC0402N_PAN")
      (description "No Description Available")
      (fields
        (field (name "MANUFACTURER_PART_NUMBER") "ERJ-2GEJ433X")
        (field (name "COPYRIGHT") "Copyright (C) 2025 Ultra Librarian. All rights reserved.")
      )
      (libsource (lib "resistor") (part "0402"))
    )
    (comp (ref "R26")
      (value "5.1K")
      (footprint "RC0402N_PAN")
      (description "No Description Available")
      (fields
        (field (name "MANUFACTURER_PART_NUMBER") "ERJ-2GEJ433X")
        (field (name "COPYRIGHT") "Copyright (C) 2025 Ultra Librarian. All rights reserved.")
      )
      (libsource (lib "resistor") (part "0402"))
    )
    (comp (ref "R27")
      (value "3.3K")
      (footprint "RC0402N_PAN")
      (description "No Description Available")
      (fields
        (field (name "MANUFACTURER_PART_NUMBER") "ERJ-2GEJ433X")
        (field (name "COPYRIGHT") "Copyright (C) 2025 Ultra Librarian. All rights reserved.")
      )
      (libsource (lib "resistor") (part "0402"))
    )
    (comp (ref "R28")
      (value "3.3K")
      (footprint "RC0402N_PAN")
      (description "No Description Available")
      (fields
        (field (name "MANUFACTURER_PART_NUMBER") "ERJ-2GEJ433X")
        (field (name "COPYRIGHT") "Copyright (C) 2025 Ultra Librarian. All rights reserved.")
      )
      (libsource (lib "resistor") (part "0402"))
    )
    (comp (ref "R29")
      (value "22R")
      (footprint "RC0603N_PAN")
      (description "No Description Available")
      (fields
        (field (name "MANUFACTURER_PART_NUMBER") "ERJ-3GEYJ6R8V")
        (field (name "COPYRIGHT") "Copyright (C) 2025 Ultra Librarian. All rights reserved.")
      )
      (libsource (lib "resistor") (part "0603"))
    )
    (comp (ref "R30")
      (value "22R")
      (footprint "RC0603N_PAN")
      (description "No Description Available")
      (fields
        (field (name "MANUFACTURER_PART_NUMBER") "ERJ-3GEYJ6R8V")
        (field (name "COPYRIGHT") "Copyright (C) 2025 Ultra Librarian. All rights reserved.")
      )
      (libsource (lib "resistor") (part "0603"))
    )
    (comp (ref "R31")
      (value "3.3K")
      (footprint "RC0603N_PAN")
      (description "No Description Available")
      (fields
        (field (name "MANUFACTURER_PART_NUMBER") "ERJ-3GEYJ6R8V")
        (field (name "COPYRIGHT") "Copyright (C) 2025 Ultra Librarian. All rights reserved.")
      )
      (libsource (lib "resistor") (part "0603"))
    )
    (comp (ref "R32")
      (value "1K")
      (footprint "RC0402N_PAN")
      (description "No Description Available")
      (fields
        (field (name "MANUFACTURER_PART_NUMBER") "ERJ-2GEJ433X")
        (field (name "COPYRIGHT") "Copyright (C) 2025 Ultra Librarian. All rights reserved.")
      )
      (libsource (lib "resistor") (part "0402"))
    )
    (comp (ref "R33")
      (value "3.3K")
      (footprint "RC0402N_PAN")
      (description "No Description Available")
      (fields
        (field (name "MANUFACTURER_PART_NUMBER") "ERJ-2GEJ433X")
        (field (name "COPYRIGHT") "Copyright (C) 2025 Ultra Librarian. All rights reserved.")
      )
      (libsource (lib "resistor") (part "0402"))
    )
    (comp (ref "R34")
      (value "3.3K")
      (footprint "RC0402N_PAN")
      (description "No Description Available")
      (fields
        (field (name "MANUFACTURER_PART_NUMBER") "ERJ-2GEJ433X")
        (field (name "COPYRIGHT") "Copyright (C) 2025 Ultra Librarian. All rights reserved.")
      )
      (libsource (lib "resistor") (part "0402"))
    )
    (comp (ref "R35")
      (value "ERJ-2GEJ433X")
      (footprint "RC0402N_PAN")
      (description "No Description Available")
      (fields (field (name "COPYRIGHT") "Copyright (C) 2025 Ultra Librarian. All rights reserved."))
      (libsource (lib "resistor") (part "0402"))
    )
    (comp (ref "R36")
      (value "3.3K")
      (footprint "RC0603N_PAN")
      (description "No Description Available")
      (fields
        (field (name "MANUFACTURER_PART_NUMBER") "ERJ-3GEYJ6R8V")
        (field (name "COPYRIGHT") "Copyright (C) 2025 Ultra Librarian. All rights reserved.")
      )
      (libsource (lib "resistor") (part "0603"))
    )
    (comp (ref "R37")
      (value "22R")
      (footprint "RC0603N_PAN")
      (description "No Description Available")
      (fields
        (field (name "MANUFACTURER_PART_NUMBER") "ERJ-3GEYJ6R8V")
        (field (name "COPYRIGHT") "Copyright (C) 2025 Ultra Librarian. All rights reserved.")
      )
      (libsource (lib "resistor") (part "0603"))
    )
    (comp (ref "R38")
      (value "22R")
      (footprint "RC0603N_PAN")
      (description "No Description Available")
      (fields
        (field (name "MANUFACTURER_PART_NUMBER") "ERJ-3GEYJ6R8V")
        (field (name "COPYRIGHT") "Copyright (C) 2025 Ultra Librarian. All rights reserved.")
      )
      (libsource (lib "resistor") (part "0603"))
    )
    (comp (ref "R39")
      (value "3.3K")
      (footprint "RC0603N_PAN")
      (description "No Description Available")
      (fields
        (field (name "MANUFACTURER_PART_NUMBER") "ERJ-3GEYJ6R8V")
        (field (name "COPYRIGHT") "Copyright (C) 2025 Ultra Librarian. All rights reserved.")
      )
      (libsource (lib "resistor") (part "0603"))
    )
    (comp (ref "R40")
      (value "3.3K")
      (footprint "RC0603N_PAN")
      (description "No Description Available")
      (fields
        (field (name "MANUFACTURER_PART_NUMBER") "ERJ-3GEYJ6R8V")
        (field (name "COPYRIGHT") "Copyright (C) 2025 Ultra Librarian. All rights reserved.")
      )
      (libsource (lib "resistor") (part "0603"))
    )
    (comp (ref "R41")
      (value "3.3K")
      (footprint "RC0603N_PAN")
      (description "No Description Available")
      (fields
        (field (name "MANUFACTURER_PART_NUMBER") "ERJ-3GEYJ6R8V")
        (field (name "COPYRIGHT") "Copyright (C) 2025 Ultra Librarian. All rights reserved.")
      )
      (libsource (lib "resistor") (part "0603"))
    )
    (comp (ref "R42")
      (value "3.3K")
      (footprint "RC0603N_PAN")
      (description "No Description Available")
      (fields
        (field (name "MANUFACTURER_PART_NUMBER") "ERJ-3GEYJ6R8V")
        (field (name "COPYRIGHT") "Copyright (C) 2025 Ultra Librarian. All rights reserved.")
      )
      (libsource (lib "resistor") (part "0603"))
    )
    (comp (ref "R43")
      (value "3.3K")
      (footprint "RC0603N_PAN")
      (description "No Description Available")
      (fields
        (field (name "MANUFACTURER_PART_NUMBER") "ERJ-3GEYJ6R8V")
        (field (name "COPYRIGHT") "Copyright (C) 2025 Ultra Librarian. All rights reserved.")
      )
      (libsource (lib "resistor") (part "0603"))
    )
    (comp (ref "R44")
      (value "3.3K")
      (footprint "RC0603N_PAN")
      (description "No Description Available")
      (fields
        (field (name "MANUFACTURER_PART_NUMBER") "ERJ-3GEYJ6R8V")
        (field (name "COPYRIGHT") "Copyright (C) 2025 Ultra Librarian. All rights reserved.")
      )
      (libsource (lib "resistor") (part "0603"))
    )
    (comp (ref "R45")
      (value "3.3K")
      (footprint "RC0603N_PAN")
      (description "No Description Available")
      (fields
        (field (name "MANUFACTURER_PART_NUMBER") "ERJ-3GEYJ6R8V")
        (field (name "COPYRIGHT") "Copyright (C) 2025 Ultra Librarian. All rights reserved.")
      )
      (libsource (lib "resistor") (part "0603"))
    )
    (comp (ref "U1")
      (value "DRV8301DCAR")
      (footprint "SOP50P810X120-57N")
      (description "ç”µæœºé©±åŠ¨å™¨åŠŸçŽ‡MOSFET SPI 56-HTSSOP")
      (fields (field (name "DIGI-KEY_PART_NUMBER") "296-29433-1-ND") (field (name "MF") "Texas Instruments"))
      (libsource (lib "ffb_wheel") (part "DRV8301DCAR"))
    )
    (comp (ref "U2")
      (value "SN65HVD232DR")
      (footprint "D8")
      (description "3.3 V CAN Transceiver 8-SOIC -40 to 85")
      (fields (field (name "COPYRIGHT") "Copyright (C) 2025 Ultra Librarian. All rights reserved."))
      (libsource (lib "ffb_wheel") (part "SN65HVD232DR"))
    )
    (comp (ref "U3")
      (value "STM32F405RGT6")
      (footprint "QFP50P1200X1200X160-64N")
      (fields (field (name "MF") "STMicroelectronics"))
      (libsource (lib "ffb_wheel") (part "STM32F405RGT6"))
    )
    (comp (ref "U4")
      (value "LP5907MFX-3.3/NOPB")
      (footprint "DBV0005A_L")
      (fields (field (name "COPYRIGHT") "Copyright (C) 2025 Ultra Librarian. All rights reserved."))
      (libsource (lib "ffb_wheel") (part "LP5907MFX-3.3NOPB"))
    )
    (comp (ref "U5")
      (value "B3U-1000P")
      (footprint "B3U-1000P")
      (description "Description")
      (fields (field (name "COPYRIGHT") "Copyright (C) 2025 Ultra Librarian. All rights reserved."))
      (libsource (lib "ffb_wheel") (part "B3U-1000P"))
    )
    (comp (ref "U6")
      (value "AMS1117-3.3")
      (footprint "SOT-223_UMW")
      (description "Description")
      (fields (field (name "COPYRIGHT") "Copyright (C) 2025 Ultra Librarian. All rights reserved."))
      (libsource (lib "ffb_wheel") (part "AMS1117-3.3"))
    )
    (comp (ref "U7")
      (value "B3U-1000P")
      (footprint "B3U-1000P")
      (description "Description")
      (fields (field (name "COPYRIGHT") "Copyright (C) 2025 Ultra Librarian. All rights reserved."))
      (libsource (lib "") (part "B3U-1000P_1"))
    )
    (comp (ref "U8")
      (value "AS5047P-ATSM")
      (footprint "SOP65P640X120-14N")
      (description "Rotary Encoder Magnetic Programmable PWM -")
      (fields (field (name "MF") "ams"))
      (libsource (lib "ffb_wheel") (part "AS5047P-ATSM"))
    )
    (comp (ref "Y1")
      (value "ABM3-8.000MHZ-D2Y-T")
      (footprint "XTAL_ABM3-8.000MHZ-D2Y-T")
      (description "8 MHz Â±20ppm Crystal 18pF 140 Ohms 2-SMD, No Lead")
      (fields (field (name "MF") "Abracon"))
      (libsource (lib "ffb_wheel") (part "ABM3-8.000MHZ-D2Y-T"))
    )
  )
  (nets
    (net (code "1") (name "/0GH_A") (class "Default")
      (node (ref "R7") (pin "1") (pinfunction "1_1") (pintype "passive"))
      (node (ref "U1") (pin "47") (pinfunction "GH_A_47") (pintype "output"))
    )
    (net (code "2") (name "/0GH_B") (class "Default")
      (node (ref "R6") (pin "1") (pinfunction "1_1") (pintype "passive"))
      (node (ref "U1") (pin "42") (pinfunction "GH_B_42") (pintype "output"))
    )
    (net (code "3") (name "/0GH_C") (class "Default")
      (node (ref "R5") (pin "1") (pinfunction "1_1") (pintype "passive"))
      (node (ref "U1") (pin "37") (pinfunction "GH_C_37") (pintype "output"))
    )
    (net (code "4") (name "/0GL_A") (class "Default")
      (node (ref "R11") (pin "1") (pinfunction "1_1") (pintype "passive"))
      (node (ref "U1") (pin "45") (pinfunction "GL_A_45") (pintype "output"))
    )
    (net (code "5") (name "/0GL_B") (class "Default")
      (node (ref "R10") (pin "1") (pinfunction "1_1") (pintype "passive"))
      (node (ref "U1") (pin "40") (pinfunction "GL_B_40") (pintype "output"))
    )
    (net (code "6") (name "/0GL_C") (class "Default")
      (node (ref "R9") (pin "1") (pinfunction "1_1") (pintype "passive"))
      (node (ref "U1") (pin "35") (pinfunction "GL_C_35") (pintype "output"))
    )
    (net (code "7") (name "/0SH_A") (class "Default")
      (node (ref "C12") (pin "1") (pinfunction "1_1") (pintype "passive"))
      (node (ref "J2") (pin "1") (pinfunction "1_1") (pintype "passive"))
      (node (ref "Q3") (pin "1") (pinfunction "S_1") (pintype "passive"))
      (node (ref "Q3") (pin "2") (pinfunction "S_2") (pintype "passive"))
      (node (ref "Q3") (pin "3") (pinfunction "S_3") (pintype "passive"))
      (node (ref "Q6") (pin "5") (pinfunction "D_5") (pintype "passive"))
      (node (ref "U1") (pin "46") (pinfunction "SH_A_46") (pintype "input"))
    )
    (net (code "8") (name "/0SH_B") (class "Default")
      (node (ref "C14") (pin "1") (pinfunction "1_1") (pintype "passive"))
      (node (ref "J2") (pin "2") (pinfunction "2_2") (pintype "passive"))
      (node (ref "Q2") (pin "1") (pinfunction "S_1") (pintype "passive"))
      (node (ref "Q2") (pin "2") (pinfunction "S_2") (pintype "passive"))
      (node (ref "Q2") (pin "3") (pinfunction "S_3") (pintype "passive"))
      (node (ref "Q5") (pin "5") (pinfunction "D_5") (pintype "passive"))
      (node (ref "U1") (pin "41") (pinfunction "SH_B_41") (pintype "input"))
    )
    (net (code "9") (name "/0SH_C") (class "Default")
      (node (ref "C16") (pin "1") (pinfunction "1_1") (pintype "passive"))
      (node (ref "J2") (pin "3") (pinfunction "3_3") (pintype "passive"))
      (node (ref "Q1") (pin "1") (pinfunction "S_1") (pintype "passive"))
      (node (ref "Q1") (pin "2") (pinfunction "S_2") (pintype "passive"))
      (node (ref "Q1") (pin "3") (pinfunction "S_3") (pintype "passive"))
      (node (ref "Q4") (pin "5") (pinfunction "D_5") (pintype "passive"))
      (node (ref "U1") (pin "36") (pinfunction "SH_C_36") (pintype "input"))
    )
    (net (code "10") (name "/0SL_B") (class "Default")
      (node (ref "Q5") (pin "1") (pinfunction "S_1") (pintype "passive"))
      (node (ref "Q5") (pin "2") (pinfunction "S_2") (pintype "passive"))
      (node (ref "Q5") (pin "3") (pinfunction "S_3") (pintype "passive"))
      (node (ref "R13") (pin "4") (pinfunction "4_4") (pintype "passive"))
      (node (ref "U1") (pin "39") (pinfunction "SL_B_39") (pintype "input"))
    )
    (net (code "11") (name "/0SL_C") (class "Default")
      (node (ref "Q4") (pin "1") (pinfunction "S_1") (pintype "passive"))
      (node (ref "Q4") (pin "2") (pinfunction "S_2") (pintype "passive"))
      (node (ref "Q4") (pin "3") (pinfunction "S_3") (pintype "passive"))
      (node (ref "R12") (pin "4") (pinfunction "4_4") (pintype "passive"))
      (node (ref "U1") (pin "34") (pinfunction "SL_C_34") (pintype "input"))
    )
    (net (code "12") (name "/0SN1") (class "Default")
      (node (ref "C19") (pin "2") (pinfunction "2_2") (pintype "passive"))
      (node (ref "R15") (pin "1") (pinfunction "1_1") (pintype "passive"))
      (node (ref "U1") (pin "33") (pinfunction "SN1_33") (pintype "input"))
    )
    (net (code "13") (name "/0SN2") (class "Default")
      (node (ref "C23") (pin "2") (pinfunction "2_2") (pintype "passive"))
      (node (ref "R18") (pin "1") (pinfunction "1_1") (pintype "passive"))
      (node (ref "U1") (pin "31") (pinfunction "SN2_31") (pintype "input"))
    )
    (net (code "14") (name "/AUX_H") (class "Default")
      (node (ref "1") (pin "2") (pinfunction "HI_2") (pintype "input"))
      (node (ref "R19") (pin "2") (pinfunction "2_2") (pintype "passive"))
      (node (ref "U3") (pin "30") (pinfunction "PB11_30") (pintype "bidirectional"))
    )
    (net (code "15") (name "/AUX_L") (class "Default")
      (node (ref "1") (pin "3") (pinfunction "LI_3") (pintype "input"))
      (node (ref "R21") (pin "2") (pinfunction "2_2") (pintype "passive"))
      (node (ref "U3") (pin "29") (pinfunction "PB10_29") (pintype "bidirectional"))
    )
    (net (code "16") (name "/AUX_TEMP") (class "Default")
      (node (ref "C33") (pin "1") (pinfunction "1_1") (pintype "passive"))
      (node (ref "R23") (pin "2") (pinfunction "2_2") (pintype "passive"))
      (node (ref "R26") (pin "1") (pinfunction "1_1") (pintype "passive"))
      (node (ref "U3") (pin "21") (pinfunction "PA5/SPI1_SCK_21") (pintype "bidirectional"))
    )
    (net (code "17") (name "/BOOT0") (class "Default")
      (node (ref "C41") (pin "2") (pinfunction "2_2") (pintype "passive"))
      (node (ref "R31") (pin "1") (pinfunction "1_1") (pintype "passive"))
      (node (ref "U3") (pin "60") (pinfunction "BOOT0_60") (pintype "bidirectional"))
      (node (ref "U5") (pin "1") (pinfunction "1_1") (pintype "passive"))
    )
    (net (code "18") (name "/CAN_D") (class "Default")
      (node (ref "U2") (pin "1") (pinfunction "D_1") (pintype "input"))
      (node (ref "U3") (pin "62") (pinfunction "PB9_62") (pintype "bidirectional"))
    )
    (net (code "19") (name "/CAN_H") (class "Default")
      (node (ref "J9") (pin "2") (pinfunction "2_2") (pintype "passive"))
      (node (ref "R17") (pin "1") (pinfunction "1_1") (pintype "passive"))
      (node (ref "U2") (pin "7") (pinfunction "CANH_7") (pintype "output"))
    )
    (net (code "20") (name "/CAN_L") (class "Default")
      (node (ref "J3") (pin "2") (pinfunction "2_2") (pintype "passive"))
      (node (ref "J9") (pin "1") (pinfunction "1_1") (pintype "passive"))
      (node (ref "U2") (pin "6") (pinfunction "CANL_6") (pintype "output"))
    )
    (net (code "21") (name "/CAN_R") (class "Default")
      (node (ref "U2") (pin "4") (pinfunction "R_4") (pintype "input"))
      (node (ref "U3") (pin "61") (pinfunction "PB8_61") (pintype "bidirectional"))
    )
    (net (code "22") (name "/DN") (class "Default")
      (node (ref "J5") (pin "A7") (pinfunction "DN1_A7") (pintype "bidirectional"))
      (node (ref "J5") (pin "B7") (pinfunction "DN2_B7") (pintype "bidirectional"))
      (node (ref "Q9") (pin "2") (pinfunction "S_2") (pintype "passive"))
      (node (ref "R38") (pin "2") (pinfunction "2_2") (pintype "passive"))
    )
    (net (code "23") (name "/DP") (class "Default")
      (node (ref "J5") (pin "A6") (pinfunction "DP1_A6") (pintype "bidirectional"))
      (node (ref "J5") (pin "B6") (pinfunction "DP2_B6") (pintype "bidirectional"))
      (node (ref "Q9") (pin "1") (pinfunction "D_1") (pintype "passive"))
      (node (ref "R37") (pin "2") (pinfunction "2_2") (pintype "passive"))
    )
    (net (code "24") (name "/EN_GATE") (class "Default")
      (node (ref "U1") (pin "16") (pinfunction "EN_GATE_16") (pintype "input"))
      (node (ref "U3") (pin "33") (pinfunction "PB12_33") (pintype "bidirectional"))
    )
    (net (code "25") (name "/GPIO_1") (class "Default")
      (node (ref "J8") (pin "6") (pinfunction "6_6") (pintype "passive"))
      (node (ref "R39") (pin "2") (pinfunction "2_2") (pintype "passive"))
    )
    (net (code "26") (name "/GPIO_1_FLT") (class "Default")
      (node (ref "C51") (pin "2") (pinfunction "2_2") (pintype "passive"))
      (node (ref "R39") (pin "1") (pinfunction "1_1") (pintype "passive"))
      (node (ref "U3") (pin "14") (pinfunction "PA0/WKUP_14") (pintype "bidirectional"))
    )
    (net (code "27") (name "/GPIO_2") (class "Default")
      (node (ref "J8") (pin "5") (pinfunction "5_5") (pintype "passive"))
      (node (ref "R40") (pin "2") (pinfunction "2_2") (pintype "passive"))
    )
    (net (code "28") (name "/GPIO_2_FLT") (class "Default")
      (node (ref "C52") (pin "2") (pinfunction "2_2") (pintype "passive"))
      (node (ref "R40") (pin "1") (pinfunction "1_1") (pintype "passive"))
      (node (ref "U3") (pin "15") (pinfunction "PA1/USART2_RTS_15") (pintype "bidirectional"))
    )
    (net (code "29") (name "/GPIO_3") (class "Default")
      (node (ref "J8") (pin "4") (pinfunction "4_4") (pintype "passive"))
      (node (ref "U3") (pin "16") (pinfunction "PA2/USART2_TX_16") (pintype "bidirectional"))
      (node (ref "U3") (pin "17") (pinfunction "PA3/USART2_RX_17") (pintype "bidirectional"))
    )
    (net (code "30") (name "/GPIO_4") (class "Default")
      (node (ref "J8") (pin "3") (pinfunction "3_3") (pintype "passive"))
    )
    (net (code "31") (name "/GPIO_6") (class "Default")
      (node (ref "J6") (pin "2") (pinfunction "2_2") (pintype "passive"))
      (node (ref "R41") (pin "2") (pinfunction "2_2") (pintype "passive"))
    )
    (net (code "32") (name "/GPIO_6_FLT") (class "Default")
      (node (ref "C53") (pin "2") (pinfunction "2_2") (pintype "passive"))
      (node (ref "R41") (pin "1") (pinfunction "1_1") (pintype "passive"))
      (node (ref "U3") (pin "28") (pinfunction "PB2/BOOT1_28") (pintype "bidirectional"))
    )
    (net (code "33") (name "/GPIO_7") (class "Default")
      (node (ref "R42") (pin "2") (pinfunction "2_2") (pintype "passive"))
      (node (ref "U8") (pin "1") (pinfunction "CSN_1") (pintype "input"))
    )
    (net (code "34") (name "/GPIO_7_FLT") (class "Default")
      (node (ref "C54") (pin "2") (pinfunction "2_2") (pintype "passive"))
      (node (ref "R42") (pin "1") (pinfunction "1_1") (pintype "passive"))
      (node (ref "U3") (pin "50") (pinfunction "PA15_50") (pintype "bidirectional"))
    )
    (net (code "35") (name "/M0_AH") (class "Default")
      (node (ref "U1") (pin "17") (pinfunction "INH_A_17") (pintype "input"))
      (node (ref "U3") (pin "41") (pinfunction "PA8_41") (pintype "bidirectional"))
    )
    (net (code "36") (name "/M0_AL") (class "Default")
      (node (ref "U1") (pin "18") (pinfunction "INL_A_18") (pintype "input"))
      (node (ref "U3") (pin "34") (pinfunction "PB13_34") (pintype "bidirectional"))
    )
    (net (code "37") (name "/M0_BH") (class "Default")
      (node (ref "U1") (pin "19") (pinfunction "INH_B_19") (pintype "input"))
      (node (ref "U3") (pin "42") (pinfunction "PA9_42") (pintype "bidirectional"))
    )
    (net (code "38") (name "/M0_BL") (class "Default")
      (node (ref "U1") (pin "20") (pinfunction "INL_B_20") (pintype "input"))
      (node (ref "U3") (pin "35") (pinfunction "PB14_35") (pintype "bidirectional"))
    )
    (net (code "39") (name "/M0_CL") (class "Default")
      (node (ref "U1") (pin "22") (pinfunction "INL_C_22") (pintype "input"))
      (node (ref "U3") (pin "36") (pinfunction "PB15_36") (pintype "bidirectional"))
    )
    (net (code "40") (name "/M0_ENC_A") (class "Default")
      (node (ref "J7") (pin "4") (pinfunction "4_4") (pintype "passive"))
      (node (ref "R43") (pin "2") (pinfunction "2_2") (pintype "passive"))
      (node (ref "U3") (pin "56") (pinfunction "PB4_56") (pintype "bidirectional"))
    )
    (net (code "41") (name "/M0_ENC_B") (class "Default")
      (node (ref "J7") (pin "3") (pinfunction "3_3") (pintype "passive"))
      (node (ref "R44") (pin "2") (pinfunction "2_2") (pintype "passive"))
      (node (ref "U3") (pin "57") (pinfunction "PB5_57") (pintype "bidirectional"))
    )
    (net (code "42") (name "/M0_ENC_Z") (class "Default")
      (node (ref "J7") (pin "2") (pinfunction "2_2") (pintype "passive"))
      (node (ref "R45") (pin "2") (pinfunction "2_2") (pintype "passive"))
      (node (ref "U3") (pin "40") (pinfunction "PC9_40") (pintype "bidirectional"))
    )
    (net (code "43") (name "/M0_SO1") (class "Default")
      (node (ref "C17") (pin "2") (pinfunction "2_2") (pintype "passive"))
      (node (ref "R14") (pin "1") (pinfunction "1_1") (pintype "passive"))
      (node (ref "U3") (pin "8") (pinfunction "PC0_8") (pintype "bidirectional"))
    )
    (net (code "44") (name "/M0_SO2") (class "Default")
      (node (ref "C25") (pin "2") (pinfunction "2_2") (pintype "passive"))
      (node (ref "R16") (pin "1") (pinfunction "1_1") (pintype "passive"))
      (node (ref "U3") (pin "9") (pinfunction "PC1_9") (pintype "bidirectional"))
    )
    (net (code "45") (name "/M0_TEMP") (class "Default")
      (node (ref "C34") (pin "1") (pinfunction "1_1") (pintype "passive"))
      (node (ref "R24") (pin "2") (pinfunction "2_2") (pintype "passive"))
      (node (ref "R27") (pin "1") (pinfunction "1_1") (pintype "passive"))
      (node (ref "U3") (pin "25") (pinfunction "PC5_25") (pintype "bidirectional"))
    )
    (net (code "46") (name "/M0_nCS") (class "Default")
      (node (ref "U1") (pin "8") (pinfunction "~{SCS}_8") (pintype "input"))
      (node (ref "U3") (pin "2") (pinfunction "PC13/RTC_OUT_2") (pintype "bidirectional"))
    )
    (net (code "47") (name "/MO_CH") (class "Default")
      (node (ref "U1") (pin "21") (pinfunction "INH_C_21") (pintype "input"))
      (node (ref "U3") (pin "43") (pinfunction "PA10_43") (pintype "bidirectional"))
    )
    (net (code "48") (name "/RESET") (class "Default")
      (node (ref "C36") (pin "1") (pinfunction "1_1") (pintype "passive"))
      (node (ref "C46") (pin "2") (pinfunction "2_2") (pintype "passive"))
      (node (ref "J4") (pin "5") (pinfunction "5_5") (pintype "passive"))
      (node (ref "R36") (pin "1") (pinfunction "1_1") (pintype "passive"))
      (node (ref "U3") (pin "7") (pinfunction "NRST_7") (pintype "bidirectional"))
      (node (ref "U7") (pin "1") (pinfunction "1_1") (pintype "passive"))
    )
    (net (code "49") (name "/S1_N") (class "Default")
      (node (ref "R13") (pin "3") (pinfunction "3_3") (pintype "passive"))
      (node (ref "R15") (pin "2") (pinfunction "2_2") (pintype "passive"))
    )
    (net (code "50") (name "/S1_P") (class "Default")
      (node (ref "C19") (pin "1") (pinfunction "1_1") (pintype "passive"))
      (node (ref "R13") (pin "2") (pinfunction "2_2") (pintype "passive"))
      (node (ref "U1") (pin "32") (pinfunction "SP1_32") (pintype "input"))
    )
    (net (code "51") (name "/S2_N") (class "Default")
      (node (ref "R12") (pin "3") (pinfunction "3_3") (pintype "passive"))
      (node (ref "R18") (pin "2") (pinfunction "2_2") (pintype "passive"))
    )
    (net (code "52") (name "/S2_P") (class "Default")
      (node (ref "C23") (pin "1") (pinfunction "1_1") (pintype "passive"))
      (node (ref "R12") (pin "2") (pinfunction "2_2") (pintype "passive"))
      (node (ref "U1") (pin "30") (pinfunction "SP2_30") (pintype "input"))
    )
    (net (code "53") (name "/SPI_MISO") (class "Default")
      (node (ref "J6") (pin "4") (pinfunction "4_4") (pintype "passive"))
      (node (ref "U1") (pin "10") (pinfunction "SDO_10") (pintype "output"))
      (node (ref "U3") (pin "52") (pinfunction "PC11_52") (pintype "bidirectional"))
      (node (ref "U8") (pin "3") (pinfunction "MISO_3") (pintype "output"))
    )
    (net (code "54") (name "/SPI_MOSI") (class "Default")
      (node (ref "J6") (pin "5") (pinfunction "5_5") (pintype "passive"))
      (node (ref "U1") (pin "9") (pinfunction "SDI_9") (pintype "input"))
      (node (ref "U3") (pin "53") (pinfunction "PC12_53") (pintype "bidirectional"))
      (node (ref "U8") (pin "4") (pinfunction "MOSI_4") (pintype "input"))
    )
    (net (code "55") (name "/SPI_SCK") (class "Default")
      (node (ref "J6") (pin "3") (pinfunction "3_3") (pintype "passive"))
      (node (ref "U1") (pin "11") (pinfunction "SCLK_11") (pintype "input"))
      (node (ref "U3") (pin "51") (pinfunction "PC10_51") (pintype "bidirectional"))
      (node (ref "U8") (pin "2") (pinfunction "CLK_2") (pintype "input"))
    )
    (net (code "56") (name "/SWCLK") (class "Default")
      (node (ref "R30") (pin "2") (pinfunction "2_2") (pintype "passive"))
      (node (ref "U3") (pin "49") (pinfunction "PA14/JTCK-SWCLK_49") (pintype "bidirectional"))
    )
    (net (code "57") (name "/SWDIO") (class "Default")
      (node (ref "R29") (pin "2") (pinfunction "2_2") (pintype "passive"))
      (node (ref "U3") (pin "46") (pinfunction "PA13/JMS-SWDIO_46") (pintype "bidirectional"))
    )
    (net (code "58") (name "/USB_N") (class "Default")
      (node (ref "R38") (pin "1") (pinfunction "1_1") (pintype "passive"))
      (node (ref "U3") (pin "44") (pinfunction "PA11_44") (pintype "bidirectional"))
    )
    (net (code "59") (name "/USB_P") (class "Default")
      (node (ref "R37") (pin "1") (pinfunction "1_1") (pintype "passive"))
      (node (ref "U3") (pin "45") (pinfunction "PA12_45") (pintype "bidirectional"))
    )
    (net (code "60") (name "/VBUS_S") (class "Default")
      (node (ref "C35") (pin "1") (pinfunction "1_1") (pintype "passive"))
      (node (ref "R25") (pin "2") (pinfunction "2_2") (pintype "passive"))
      (node (ref "R28") (pin "1") (pinfunction "1_1") (pintype "passive"))
      (node (ref "U3") (pin "22") (pinfunction "PA6/SPI1_MISO_22") (pintype "bidirectional"))
    )
    (net (code "61") (name "/nFAULT") (class "Default")
      (node (ref "U1") (pin "6") (pinfunction "~{FAULT}_6") (pintype "output"))
      (node (ref "U3") (pin "54") (pinfunction "PD2_54") (pintype "bidirectional"))
    )
    (net (code "62") (name "3V3") (class "Default")
      (node (ref "C29") (pin "2") (pinfunction "2_2") (pintype "passive"))
      (node (ref "C39") (pin "1") (pinfunction "1_1") (pintype "passive"))
      (node (ref "C44") (pin "1") (pinfunction "1_1") (pintype "passive"))
      (node (ref "C45") (pin "1") (pinfunction "1_1") (pintype "passive"))
      (node (ref "C47") (pin "1") (pinfunction "1_1") (pintype "passive"))
      (node (ref "C48") (pin "1") (pinfunction "1_1") (pintype "passive"))
      (node (ref "C50") (pin "2") (pinfunction "2_2") (pintype "passive"))
      (node (ref "D3") (pin "POS") (pinfunction "POS_POS") (pintype "passive"))
      (node (ref "J4") (pin "1") (pinfunction "1_1") (pintype "passive"))
      (node (ref "J6") (pin "1") (pinfunction "1_1") (pintype "passive"))
      (node (ref "R31") (pin "2") (pinfunction "2_2") (pintype "passive"))
      (node (ref "R36") (pin "2") (pinfunction "2_2") (pintype "passive"))
      (node (ref "R43") (pin "1") (pinfunction "1_1") (pintype "passive"))
      (node (ref "R44") (pin "1") (pinfunction "1_1") (pintype "passive"))
      (node (ref "R45") (pin "1") (pinfunction "1_1") (pintype "passive"))
      (node (ref "U1") (pin "49") (pinfunction "VDD_SPI_49") (pintype "input"))
      (node (ref "U2") (pin "3") (pinfunction "VCC_3") (pintype "power_in"))
      (node (ref "U3") (pin "1") (pinfunction "VBAT_1") (pintype "power_in"))
      (node (ref "U3") (pin "19") (pinfunction "VDD_19") (pintype "power_in"))
      (node (ref "U3") (pin "32") (pinfunction "VDD_32") (pintype "power_in"))
      (node (ref "U3") (pin "48") (pinfunction "VDD_48") (pintype "power_in"))
      (node (ref "U3") (pin "64") (pinfunction "VDD_64") (pintype "power_in"))
      (node (ref "U6") (pin "2") (pinfunction "VOUT_2") (pintype "output"))
      (node (ref "U8") (pin "11") (pinfunction "VDD_11") (pintype "power_in"))
      (node (ref "U8") (pin "12") (pinfunction "VDD3V3_12") (pintype "power_in"))
    )
    (net (code "63") (name "5V") (class "Default")
      (node (ref "C32") (pin "1") (pinfunction "1_1") (pintype "passive"))
      (node (ref "C38") (pin "1") (pinfunction "1_1") (pintype "passive"))
      (node (ref "J7") (pin "1") (pinfunction "1_1") (pintype "passive"))
      (node (ref "J8") (pin "2") (pinfunction "2_2") (pintype "passive"))
      (node (ref "L1") (pin "2") (pinfunction "2_2") (pintype "passive"))
      (node (ref "R3") (pin "2") (pinfunction "2_2") (pintype "passive"))
      (node (ref "U4") (pin "1") (pinfunction "VIN_1") (pintype "power_in"))
      (node (ref "U4") (pin "3") (pinfunction "EN_3") (pintype "input"))
      (node (ref "U6") (pin "3") (pinfunction "VIN_3") (pintype "power_in"))
    )
    (net (code "64") (name "AVCC") (class "Default")
      (node (ref "C31") (pin "1") (pinfunction "1_1") (pintype "passive"))
      (node (ref "C49") (pin "1") (pinfunction "1_1") (pintype "passive"))
      (node (ref "R23") (pin "1") (pinfunction "1_1") (pintype "passive"))
      (node (ref "R24") (pin "1") (pinfunction "1_1") (pintype "passive"))
      (node (ref "U1") (pin "24") (pinfunction "REF_24") (pintype "input"))
      (node (ref "U3") (pin "13") (pinfunction "VDDA_13") (pintype "power_in"))
      (node (ref "U4") (pin "4") (pinfunction "N_C_4") (pintype "passive"))
      (node (ref "U4") (pin "5") (pinfunction "VOUT_5") (pintype "power_in"))
    )
    (net (code "65") (name "GND") (class "Default")
      (node (ref "1") (pin "4") (pinfunction "VSS_4") (pintype "power_in"))
      (node (ref "C1") (pin "1") (pinfunction "1_1") (pintype "passive"))
      (node (ref "C10") (pin "1") (pinfunction "1_1") (pintype "passive"))
      (node (ref "C13") (pin "1") (pinfunction "1_1") (pintype "passive"))
      (node (ref "C17") (pin "1") (pinfunction "1_1") (pintype "passive"))
      (node (ref "C18") (pin "2") (pinfunction "2_2") (pintype "passive"))
      (node (ref "C2") (pin "1") (pinfunction "1_1") (pintype "passive"))
      (node (ref "C24") (pin "2") (pinfunction "2_2") (pintype "passive"))
      (node (ref "C25") (pin "1") (pinfunction "1_1") (pintype "passive"))
      (node (ref "C27") (pin "1") (pinfunction "1_1") (pintype "passive"))
      (node (ref "C28") (pin "1") (pinfunction "1_1") (pintype "passive"))
      (node (ref "C29") (pin "1") (pinfunction "1_1") (pintype "passive"))
      (node (ref "C3") (pin "1") (pinfunction "1_1") (pintype "passive"))
      (node (ref "C30") (pin "2") (pinfunction "2_2") (pintype "passive"))
      (node (ref "C31") (pin "2") (pinfunction "2_2") (pintype "passive"))
      (node (ref "C32") (pin "2") (pinfunction "2_2") (pintype "passive"))
      (node (ref "C33") (pin "2") (pinfunction "2_2") (pintype "passive"))
      (node (ref "C34") (pin "2") (pinfunction "2_2") (pintype "passive"))
      (node (ref "C35") (pin "2") (pinfunction "2_2") (pintype "passive"))
      (node (ref "C36") (pin "2") (pinfunction "2_2") (pintype "passive"))
      (node (ref "C37") (pin "1") (pinfunction "1_1") (pintype "passive"))
      (node (ref "C38") (pin "2") (pinfunction "2_2") (pintype "passive"))
      (node (ref "C39") (pin "2") (pinfunction "2_2") (pintype "passive"))
      (node (ref "C4") (pin "1") (pinfunction "1_1") (pintype "passive"))
      (node (ref "C40") (pin "1") (pinfunction "1_1") (pintype "passive"))
      (node (ref "C41") (pin "1") (pinfunction "1_1") (pintype "passive"))
      (node (ref "C42") (pin "1") (pinfunction "1_1") (pintype "passive"))
      (node (ref "C43") (pin "1") (pinfunction "1_1") (pintype "passive"))
      (node (ref "C44") (pin "2") (pinfunction "2_2") (pintype "passive"))
      (node (ref "C45") (pin "2") (pinfunction "2_2") (pintype "passive"))
      (node (ref "C46") (pin "1") (pinfunction "1_1") (pintype "passive"))
      (node (ref "C47") (pin "2") (pinfunction "2_2") (pintype "passive"))
      (node (ref "C48") (pin "2") (pinfunction "2_2") (pintype "passive"))
      (node (ref "C49") (pin "2") (pinfunction "2_2") (pintype "passive"))
      (node (ref "C5") (pin "1") (pinfunction "1_1") (pintype "passive"))
      (node (ref "C50") (pin "1") (pinfunction "1_1") (pintype "passive"))
      (node (ref "C51") (pin "1") (pinfunction "1_1") (pintype "passive"))
      (node (ref "C52") (pin "1") (pinfunction "1_1") (pintype "passive"))
      (node (ref "C53") (pin "1") (pinfunction "1_1") (pintype "passive"))
      (node (ref "C54") (pin "1") (pinfunction "1_1") (pintype "passive"))
      (node (ref "C6") (pin "2") (pinfunction "2_2") (pintype "passive"))
      (node (ref "C7") (pin "2") (pinfunction "2_2") (pintype "passive"))
      (node (ref "C8") (pin "2") (pinfunction "2_2") (pintype "passive"))
      (node (ref "C9") (pin "1") (pinfunction "1_1") (pintype "passive"))
      (node (ref "D1") (pin "A") (pinfunction "A_A") (pintype "passive"))
      (node (ref "J4") (pin "3") (pinfunction "3_3") (pintype "passive"))
      (node (ref "J5") (pin "A1") (pinfunction "GND_A_A1") (pintype "power_in"))
      (node (ref "J5") (pin "A12") (pinfunction "GND_A_A12") (pintype "power_in"))
      (node (ref "J5") (pin "B1") (pinfunction "GND_B_B1") (pintype "power_in"))
      (node (ref "J5") (pin "B12") (pinfunction "GND_B_B12") (pintype "power_in"))
      (node (ref "J6") (pin "6") (pinfunction "6_6") (pintype "passive"))
      (node (ref "J7") (pin "5") (pinfunction "5_5") (pintype "passive"))
      (node (ref "J8") (pin "1") (pinfunction "1_1") (pintype "passive"))
      (node (ref "Q9") (pin "3") (pinfunction "G_3") (pintype "passive"))
      (node (ref "R1") (pin "1") (pinfunction "1_1") (pintype "passive"))
      (node (ref "R19") (pin "1") (pinfunction "1_1") (pintype "passive"))
      (node (ref "R21") (pin "1") (pinfunction "1_1") (pintype "passive"))
      (node (ref "R26") (pin "2") (pinfunction "2_2") (pintype "passive"))
      (node (ref "R27") (pin "2") (pinfunction "2_2") (pintype "passive"))
      (node (ref "R28") (pin "2") (pinfunction "2_2") (pintype "passive"))
      (node (ref "R32") (pin "2") (pinfunction "2_2") (pintype "passive"))
      (node (ref "R33") (pin "1") (pinfunction "1_1") (pintype "passive"))
      (node (ref "R34") (pin "1") (pinfunction "1_1") (pintype "passive"))
      (node (ref "R35") (pin "2") (pinfunction "2_2") (pintype "passive"))
      (node (ref "R4") (pin "1") (pinfunction "1_1") (pintype "passive"))
      (node (ref "R8") (pin "1") (pinfunction "1_1") (pintype "passive"))
      (node (ref "U1") (pin "28") (pinfunction "AGND_28") (pintype "power_in"))
      (node (ref "U1") (pin "44") (pinfunction "SL_A_44") (pintype "input"))
      (node (ref "U1") (pin "57") (pinfunction "GND_57") (pintype "power_in"))
      (node (ref "U2") (pin "2") (pinfunction "GND_2") (pintype "power_in"))
      (node (ref "U3") (pin "12") (pinfunction "VSSA_12") (pintype "power_in"))
      (node (ref "U3") (pin "18") (pinfunction "VSS_18") (pintype "power_in"))
      (node (ref "U3") (pin "63") (pinfunction "VSS_63") (pintype "power_in"))
      (node (ref "U4") (pin "2") (pinfunction "GND_2") (pintype "power_in"))
      (node (ref "U5") (pin "2") (pinfunction "2_2") (pintype "passive"))
      (node (ref "U6") (pin "1") (pinfunction "GND_1") (pintype "power_in"))
      (node (ref "U7") (pin "2") (pinfunction "2_2") (pintype "passive"))
      (node (ref "U8") (pin "13") (pinfunction "GND_13") (pintype "power_in"))
      (node (ref "U8") (pin "5") (pinfunction "TEST_5") (pintype "passive"))
    )
    (net (code "66") (name "GVCC") (class "Default")
      (node (ref "1") (pin "1") (pinfunction "VDD_1") (pintype "power_in"))
      (node (ref "C13") (pin "2") (pinfunction "2_2") (pintype "passive"))
      (node (ref "C30") (pin "1") (pinfunction "1_1") (pintype "passive"))
      (node (ref "D2") (pin "A") (pinfunction "A_A") (pintype "passive"))
      (node (ref "U1") (pin "13") (pinfunction "GVDD_13") (pintype "power_in"))
    )
    (net (code "67") (name "Net-(1-HB)") (class "Default")
      (node (ref "1") (pin "8") (pinfunction "HB_8") (pintype "input"))
      (node (ref "C26") (pin "1") (pinfunction "1_1") (pintype "passive"))
      (node (ref "D2") (pin "C") (pinfunction "C_C") (pintype "passive"))
    )
    (net (code "68") (name "Net-(1-HO)") (class "Default")
      (node (ref "1") (pin "7") (pinfunction "HO_7") (pintype "output"))
      (node (ref "R20") (pin "1") (pinfunction "1_1") (pintype "passive"))
    )
    (net (code "69") (name "Net-(1-HS)") (class "Default")
      (node (ref "1") (pin "6") (pinfunction "HS_6") (pintype "input"))
      (node (ref "C26") (pin "2") (pinfunction "2_2") (pintype "passive"))
      (node (ref "P1") (pin "1") (pinfunction "1_1") (pintype "passive"))
      (node (ref "Q7") (pin "1") (pinfunction "S_1") (pintype "passive"))
      (node (ref "Q7") (pin "2") (pinfunction "S_2") (pintype "passive"))
      (node (ref "Q7") (pin "3") (pinfunction "S_3") (pintype "passive"))
      (node (ref "Q8") (pin "5") (pinfunction "D_5") (pintype "passive"))
    )
    (net (code "70") (name "Net-(1-LO)") (class "Default")
      (node (ref "1") (pin "5") (pinfunction "LO_5") (pintype "output"))
      (node (ref "R22") (pin "1") (pinfunction "1_1") (pintype "passive"))
    )
    (net (code "71") (name "Net-(C9-Pad2)") (class "Default")
      (node (ref "C9") (pin "2") (pinfunction "2_2") (pintype "passive"))
      (node (ref "R2") (pin "2") (pinfunction "2_2") (pintype "passive"))
    )
    (net (code "72") (name "Net-(C11-Pad1)") (class "Default")
      (node (ref "C11") (pin "1") (pinfunction "1_1") (pintype "passive"))
      (node (ref "D1") (pin "C") (pinfunction "C_C") (pintype "passive"))
      (node (ref "L1") (pin "1") (pinfunction "1_1") (pintype "passive"))
      (node (ref "U1") (pin "50") (pinfunction "PH_50") (pintype "output"))
      (node (ref "U1") (pin "51") (pinfunction "PH_51") (pintype "output"))
    )
    (net (code "73") (name "Net-(D3-PadNEG)") (class "Default")
      (node (ref "D3") (pin "NEG") (pinfunction "NEG_NEG") (pintype "passive"))
      (node (ref "R32") (pin "1") (pinfunction "1_1") (pintype "passive"))
    )
    (net (code "74") (name "Net-(J3-Pad1)") (class "Default")
      (node (ref "J3") (pin "1") (pinfunction "1_1") (pintype "passive"))
      (node (ref "R17") (pin "2") (pinfunction "2_2") (pintype "passive"))
    )
    (net (code "75") (name "Net-(J4-Pad2)") (class "Default")
      (node (ref "J4") (pin "2") (pinfunction "2_2") (pintype "passive"))
      (node (ref "R30") (pin "1") (pinfunction "1_1") (pintype "passive"))
    )
    (net (code "76") (name "Net-(J4-Pad4)") (class "Default")
      (node (ref "J4") (pin "4") (pinfunction "4_4") (pintype "passive"))
      (node (ref "R29") (pin "1") (pinfunction "1_1") (pintype "passive"))
    )
    (net (code "77") (name "Net-(J4-SHIELD-PadS1)") (class "Default")
      (node (ref "J4") (pin "S1") (pinfunction "SHIELD_S1") (pintype "passive"))
      (node (ref "J4") (pin "S2") (pinfunction "SHIELD_S2") (pintype "passive"))
    )
    (net (code "78") (name "Net-(J5-CC1)") (class "Default")
      (node (ref "J5") (pin "A5") (pinfunction "CC1_A5") (pintype "bidirectional"))
      (node (ref "R33") (pin "2") (pinfunction "2_2") (pintype "passive"))
    )
    (net (code "79") (name "Net-(J5-CC2)") (class "Default")
      (node (ref "J5") (pin "B5") (pinfunction "CC2_B5") (pintype "bidirectional"))
      (node (ref "R34") (pin "2") (pinfunction "2_2") (pintype "passive"))
    )
    (net (code "80") (name "Net-(J7-SHIELD-PadS1)") (class "Default")
      (node (ref "J7") (pin "S1") (pinfunction "SHIELD_S1") (pintype "passive"))
      (node (ref "J7") (pin "S2") (pinfunction "SHIELD_S2") (pintype "passive"))
    )
    (net (code "81") (name "Net-(Q1-G)") (class "Default")
      (node (ref "Q1") (pin "4") (pinfunction "G_4") (pintype "passive"))
      (node (ref "R5") (pin "2") (pinfunction "2_2") (pintype "passive"))
    )
    (net (code "82") (name "Net-(Q2-G)") (class "Default")
      (node (ref "Q2") (pin "4") (pinfunction "G_4") (pintype "passive"))
      (node (ref "R6") (pin "2") (pinfunction "2_2") (pintype "passive"))
    )
    (net (code "83") (name "Net-(Q3-G)") (class "Default")
      (node (ref "Q3") (pin "4") (pinfunction "G_4") (pintype "passive"))
      (node (ref "R7") (pin "2") (pinfunction "2_2") (pintype "passive"))
    )
    (net (code "84") (name "Net-(Q4-G)") (class "Default")
      (node (ref "Q4") (pin "4") (pinfunction "G_4") (pintype "passive"))
      (node (ref "R9") (pin "2") (pinfunction "2_2") (pintype "passive"))
    )
    (net (code "85") (name "Net-(Q5-G)") (class "Default")
      (node (ref "Q5") (pin "4") (pinfunction "G_4") (pintype "passive"))
      (node (ref "R10") (pin "2") (pinfunction "2_2") (pintype "passive"))
    )
    (net (code "86") (name "Net-(Q6-G)") (class "Default")
      (node (ref "Q6") (pin "4") (pinfunction "G_4") (pintype "passive"))
      (node (ref "R11") (pin "2") (pinfunction "2_2") (pintype "passive"))
    )
    (net (code "87") (name "Net-(Q7-G)") (class "Default")
      (node (ref "Q7") (pin "4") (pinfunction "G_4") (pintype "passive"))
      (node (ref "R20") (pin "2") (pinfunction "2_2") (pintype "passive"))
    )
    (net (code "88") (name "Net-(Q8-G)") (class "Default")
      (node (ref "Q8") (pin "4") (pinfunction "G_4") (pintype "passive"))
      (node (ref "R22") (pin "2") (pinfunction "2_2") (pintype "passive"))
    )
    (net (code "89") (name "Net-(U1-AVDD)") (class "Default")
      (node (ref "C24") (pin "1") (pinfunction "1_1") (pintype "passive"))
      (node (ref "U1") (pin "27") (pinfunction "AVDD_27") (pintype "power_in"))
    )
    (net (code "90") (name "Net-(U1-BST_A)") (class "Default")
      (node (ref "C12") (pin "2") (pinfunction "2_2") (pintype "passive"))
      (node (ref "U1") (pin "48") (pinfunction "BST_A_48") (pintype "power_in"))
    )
    (net (code "91") (name "Net-(U1-BST_B)") (class "Default")
      (node (ref "C14") (pin "2") (pinfunction "2_2") (pintype "passive"))
      (node (ref "U1") (pin "43") (pinfunction "BST_B_43") (pintype "power_in"))
    )
    (net (code "92") (name "Net-(U1-BST_BK)") (class "Default")
      (node (ref "C11") (pin "2") (pinfunction "2_2") (pintype "passive"))
      (node (ref "U1") (pin "52") (pinfunction "BST_BK_52") (pintype "power_in"))
    )
    (net (code "93") (name "Net-(U1-BST_C)") (class "Default")
      (node (ref "C16") (pin "2") (pinfunction "2_2") (pintype "passive"))
      (node (ref "U1") (pin "38") (pinfunction "BST_C_38") (pintype "power_in"))
    )
    (net (code "94") (name "Net-(U1-COMP)") (class "Default")
      (node (ref "C10") (pin "2") (pinfunction "2_2") (pintype "passive"))
      (node (ref "R2") (pin "1") (pinfunction "1_1") (pintype "passive"))
      (node (ref "U1") (pin "2") (pinfunction "COMP_2") (pintype "output"))
    )
    (net (code "95") (name "Net-(U1-CP1)") (class "Default")
      (node (ref "C15") (pin "2") (pinfunction "2_2") (pintype "passive"))
      (node (ref "U1") (pin "14") (pinfunction "CP1_14") (pintype "power_in"))
    )
    (net (code "96") (name "Net-(U1-CP2)") (class "Default")
      (node (ref "C15") (pin "1") (pinfunction "1_1") (pintype "passive"))
      (node (ref "U1") (pin "15") (pinfunction "CP2_15") (pintype "power_in"))
    )
    (net (code "97") (name "Net-(U1-DTC)") (class "Default")
      (node (ref "R8") (pin "2") (pinfunction "2_2") (pintype "passive"))
      (node (ref "U1") (pin "7") (pinfunction "DTC_7") (pintype "input"))
    )
    (net (code "98") (name "Net-(U1-DVDD)") (class "Default")
      (node (ref "C18") (pin "1") (pinfunction "1_1") (pintype "passive"))
      (node (ref "U1") (pin "23") (pinfunction "DVDD_23") (pintype "power_in"))
    )
    (net (code "99") (name "Net-(U1-PVDD1)") (class "Default")
      (node (ref "C27") (pin "2") (pinfunction "2_2") (pintype "passive"))
      (node (ref "C28") (pin "2") (pinfunction "2_2") (pintype "passive"))
      (node (ref "U1") (pin "29") (pinfunction "PVDD1_29") (pintype "power_in"))
    )
    (net (code "100") (name "Net-(U1-RT_CLK)") (class "Default")
      (node (ref "R1") (pin "2") (pinfunction "2_2") (pintype "passive"))
      (node (ref "U1") (pin "1") (pinfunction "RT_CLK_1") (pintype "input"))
    )
    (net (code "101") (name "Net-(U1-SO1)") (class "Default")
      (node (ref "R14") (pin "2") (pinfunction "2_2") (pintype "passive"))
      (node (ref "U1") (pin "25") (pinfunction "SO1_25") (pintype "output"))
    )
    (net (code "102") (name "Net-(U1-SO2)") (class "Default")
      (node (ref "R16") (pin "2") (pinfunction "2_2") (pintype "passive"))
      (node (ref "U1") (pin "26") (pinfunction "SO2_26") (pintype "output"))
    )
    (net (code "103") (name "Net-(U1-SS_TR)") (class "Default")
      (node (ref "C1") (pin "2") (pinfunction "2_2") (pintype "passive"))
      (node (ref "U1") (pin "56") (pinfunction "SS_TR_56") (pintype "input"))
    )
    (net (code "104") (name "Net-(U1-VSENSE)") (class "Default")
      (node (ref "R3") (pin "1") (pinfunction "1_1") (pintype "passive"))
      (node (ref "R4") (pin "2") (pinfunction "2_2") (pintype "passive"))
      (node (ref "U1") (pin "3") (pinfunction "VSENSE_3") (pintype "input"))
    )
    (net (code "105") (name "Net-(U3-PH0{slash}OSC_IN)") (class "Default")
      (node (ref "C37") (pin "2") (pinfunction "2_2") (pintype "passive"))
      (node (ref "U3") (pin "5") (pinfunction "PH0/OSC_IN_5") (pintype "bidirectional"))
      (node (ref "Y1") (pin "2") (pinfunction "2_2") (pintype "passive"))
    )
    (net (code "106") (name "Net-(U3-PH1{slash}OSC_OUT)") (class "Default")
      (node (ref "C40") (pin "2") (pinfunction "2_2") (pintype "passive"))
      (node (ref "U3") (pin "6") (pinfunction "PH1/OSC_OUT_6") (pintype "bidirectional"))
      (node (ref "Y1") (pin "1") (pinfunction "1_1") (pintype "passive"))
    )
    (net (code "107") (name "Net-(U3-VCAP_1)") (class "Default")
      (node (ref "C42") (pin "2") (pinfunction "2_2") (pintype "passive"))
      (node (ref "U3") (pin "31") (pinfunction "VCAP_1_31") (pintype "power_in"))
    )
    (net (code "108") (name "Net-(U3-VCAP_2)") (class "Default")
      (node (ref "C43") (pin "2") (pinfunction "2_2") (pintype "passive"))
      (node (ref "U3") (pin "47") (pinfunction "VCAP_2_47") (pintype "power_in"))
    )
    (net (code "109") (name "PGND") (class "Default")
      (node (ref "C20") (pin "1") (pinfunction "1_1") (pintype "passive"))
      (node (ref "C21") (pin "2") (pinfunction "2_2") (pintype "passive"))
      (node (ref "C22") (pin "2") (pinfunction "2_2") (pintype "passive"))
      (node (ref "J1") (pin "1") (pinfunction "1_1") (pintype "passive"))
      (node (ref "P1") (pin "2") (pinfunction "2_2") (pintype "passive"))
      (node (ref "Q6") (pin "1") (pinfunction "S_1") (pintype "passive"))
      (node (ref "Q6") (pin "2") (pinfunction "S_2") (pintype "passive"))
      (node (ref "Q6") (pin "3") (pinfunction "S_3") (pintype "passive"))
      (node (ref "Q8") (pin "1") (pinfunction "S_1") (pintype "passive"))
      (node (ref "Q8") (pin "2") (pinfunction "S_2") (pintype "passive"))
      (node (ref "Q8") (pin "3") (pinfunction "S_3") (pintype "passive"))
      (node (ref "R12") (pin "1") (pinfunction "1_1") (pintype "passive"))
      (node (ref "R13") (pin "1") (pinfunction "1_1") (pintype "passive"))
      (node (ref "R35") (pin "1") (pinfunction "1_1") (pintype "passive"))
    )
    (net (code "110") (name "PVDD") (class "Default")
      (node (ref "C2") (pin "2") (pinfunction "2_2") (pintype "passive"))
      (node (ref "C20") (pin "2") (pinfunction "2_2") (pintype "passive"))
      (node (ref "C21") (pin "1") (pinfunction "1_1") (pintype "passive"))
      (node (ref "C22") (pin "1") (pinfunction "1_1") (pintype "passive"))
      (node (ref "C3") (pin "2") (pinfunction "2_2") (pintype "passive"))
      (node (ref "C4") (pin "2") (pinfunction "2_2") (pintype "passive"))
      (node (ref "C5") (pin "2") (pinfunction "2_2") (pintype "passive"))
      (node (ref "C6") (pin "1") (pinfunction "1_1") (pintype "passive"))
      (node (ref "C7") (pin "1") (pinfunction "1_1") (pintype "passive"))
      (node (ref "C8") (pin "1") (pinfunction "1_1") (pintype "passive"))
      (node (ref "J1") (pin "2") (pinfunction "2_2") (pintype "passive"))
      (node (ref "Q1") (pin "5") (pinfunction "D_5") (pintype "passive"))
      (node (ref "Q2") (pin "5") (pinfunction "D_5") (pintype "passive"))
      (node (ref "Q3") (pin "5") (pinfunction "D_5") (pintype "passive"))
      (node (ref "Q7") (pin "5") (pinfunction "D_5") (pintype "passive"))
      (node (ref "R25") (pin "1") (pinfunction "1_1") (pintype "passive"))
      (node (ref "U1") (pin "53") (pinfunction "PVDD2_53") (pintype "power_in"))
      (node (ref "U1") (pin "54") (pinfunction "PVDD2_54") (pintype "power_in"))
    )
    (net (code "111") (name "unconnected-(J5-SBU1-PadA8)") (class "Default")
      (node (ref "J5") (pin "A8") (pinfunction "SBU1_A8") (pintype "bidirectional+no_connect"))
    )
    (net (code "112") (name "unconnected-(J5-SBU2-PadB8)") (class "Default")
      (node (ref "J5") (pin "B8") (pinfunction "SBU2_B8") (pintype "bidirectional+no_connect"))
    )
    (net (code "113") (name "unconnected-(J5-VBUS_A-PadA4)") (class "Default")
      (node (ref "J5") (pin "A4") (pinfunction "VBUS_A_A4") (pintype "passive+no_connect"))
    )
    (net (code "114") (name "unconnected-(J5-VBUS_A-PadA9)") (class "Default")
      (node (ref "J5") (pin "A9") (pinfunction "VBUS_A_A9") (pintype "passive+no_connect"))
    )
    (net (code "115") (name "unconnected-(J5-VBUS_B-PadB4)") (class "Default")
      (node (ref "J5") (pin "B4") (pinfunction "VBUS_B_B4") (pintype "passive+no_connect"))
    )
    (net (code "116") (name "unconnected-(J5-VBUS_B-PadB9)") (class "Default")
      (node (ref "J5") (pin "B9") (pinfunction "VBUS_B_B9") (pintype "passive+no_connect"))
    )
    (net (code "117") (name "unconnected-(J6-SHIELD-PadS1)") (class "Default")
      (node (ref "J6") (pin "S1") (pinfunction "SHIELD_S1") (pintype "passive"))
    )
    (net (code "118") (name "unconnected-(J6-SHIELD-PadS2)") (class "Default")
      (node (ref "J6") (pin "S2") (pinfunction "SHIELD_S2") (pintype "passive"))
    )
    (net (code "119") (name "unconnected-(J8-SHIELD-PadS1)") (class "Default")
      (node (ref "J8") (pin "S1") (pinfunction "SHIELD_S1") (pintype "passive"))
    )
    (net (code "120") (name "unconnected-(J8-SHIELD-PadS2)") (class "Default")
      (node (ref "J8") (pin "S2") (pinfunction "SHIELD_S2") (pintype "passive"))
    )
    (net (code "121") (name "unconnected-(U1-DC_CAL-Pad12)") (class "Default")
      (node (ref "U1") (pin "12") (pinfunction "DC_CAL_12") (pintype "input"))
    )
    (net (code "122") (name "unconnected-(U1-EN_BUCK-Pad55)") (class "Default")
      (node (ref "U1") (pin "55") (pinfunction "EN_BUCK_55") (pintype "input"))
    )
    (net (code "123") (name "unconnected-(U1-PWRGD-Pad4)") (class "Default")
      (node (ref "U1") (pin "4") (pinfunction "PWRGD_4") (pintype "output"))
    )
    (net (code "124") (name "unconnected-(U1-~{OCTW}-Pad5)") (class "Default")
      (node (ref "U1") (pin "5") (pinfunction "~{OCTW}_5") (pintype "output"))
    )
    (net (code "125") (name "unconnected-(U2-NC-Pad5)") (class "Default")
      (node (ref "U2") (pin "5") (pinfunction "NC_5") (pintype "passive"))
    )
    (net (code "126") (name "unconnected-(U2-NC-Pad8)") (class "Default")
      (node (ref "U2") (pin "8") (pinfunction "NC_8") (pintype "passive"))
    )
    (net (code "127") (name "unconnected-(U3-PA4{slash}USART2_CK-Pad20)") (class "Default")
      (node (ref "U3") (pin "20") (pinfunction "PA4/USART2_CK_20") (pintype "bidirectional"))
    )
    (net (code "128") (name "unconnected-(U3-PA7{slash}SPI1_MOSI-Pad23)") (class "Default")
      (node (ref "U3") (pin "23") (pinfunction "PA7/SPI1_MOSI_23") (pintype "bidirectional"))
    )
    (net (code "129") (name "unconnected-(U3-PB0-Pad26)") (class "Default")
      (node (ref "U3") (pin "26") (pinfunction "PB0_26") (pintype "bidirectional"))
    )
    (net (code "130") (name "unconnected-(U3-PB1-Pad27)") (class "Default")
      (node (ref "U3") (pin "27") (pinfunction "PB1_27") (pintype "bidirectional"))
    )
    (net (code "131") (name "unconnected-(U3-PB3-Pad55)") (class "Default")
      (node (ref "U3") (pin "55") (pinfunction "PB3_55") (pintype "bidirectional"))
    )
    (net (code "132") (name "unconnected-(U3-PB6-Pad58)") (class "Default")
      (node (ref "U3") (pin "58") (pinfunction "PB6_58") (pintype "bidirectional"))
    )
    (net (code "133") (name "unconnected-(U3-PB7-Pad59)") (class "Default")
      (node (ref "U3") (pin "59") (pinfunction "PB7_59") (pintype "bidirectional"))
    )
    (net (code "134") (name "unconnected-(U3-PC2{slash}SPI2_MISO-Pad10)") (class "Default")
      (node (ref "U3") (pin "10") (pinfunction "PC2/SPI2_MISO_10") (pintype "bidirectional"))
    )
    (net (code "135") (name "unconnected-(U3-PC3{slash}SPI2_MOSI-Pad11)") (class "Default")
      (node (ref "U3") (pin "11") (pinfunction "PC3/SPI2_MOSI_11") (pintype "bidirectional"))
    )
    (net (code "136") (name "unconnected-(U3-PC4-Pad24)") (class "Default")
      (node (ref "U3") (pin "24") (pinfunction "PC4_24") (pintype "bidirectional"))
    )
    (net (code "137") (name "unconnected-(U3-PC6-Pad37)") (class "Default")
      (node (ref "U3") (pin "37") (pinfunction "PC6_37") (pintype "bidirectional"))
    )
    (net (code "138") (name "unconnected-(U3-PC7-Pad38)") (class "Default")
      (node (ref "U3") (pin "38") (pinfunction "PC7_38") (pintype "bidirectional"))
    )
    (net (code "139") (name "unconnected-(U3-PC8-Pad39)") (class "Default")
      (node (ref "U3") (pin "39") (pinfunction "PC8_39") (pintype "bidirectional"))
    )
    (net (code "140") (name "unconnected-(U3-PC14{slash}OSC32_IN-Pad3)") (class "Default")
      (node (ref "U3") (pin "3") (pinfunction "PC14/OSC32_IN_3") (pintype "bidirectional"))
    )
    (net (code "141") (name "unconnected-(U3-PC15{slash}OSC32_OUT-Pad4)") (class "Default")
      (node (ref "U3") (pin "4") (pinfunction "PC15/OSC32_OUT_4") (pintype "bidirectional"))
    )
    (net (code "142") (name "unconnected-(U6-VOUT-Pad4)") (class "Default")
      (node (ref "U6") (pin "4") (pinfunction "VOUT_4") (pintype "output"))
    )
    (net (code "143") (name "unconnected-(U8-A-Pad7)") (class "Default")
      (node (ref "U8") (pin "7") (pinfunction "A_7") (pintype "output+no_connect"))
    )
    (net (code "144") (name "unconnected-(U8-B-Pad6)") (class "Default")
      (node (ref "U8") (pin "6") (pinfunction "B_6") (pintype "output+no_connect"))
    )
    (net (code "145") (name "unconnected-(U8-I{slash}PWM-Pad14)") (class "Default")
      (node (ref "U8") (pin "14") (pinfunction "I/PWM_14") (pintype "output+no_connect"))
    )
    (net (code "146") (name "unconnected-(U8-U-Pad10)") (class "Default")
      (node (ref "U8") (pin "10") (pinfunction "U_10") (pintype "output+no_connect"))
    )
    (net (code "147") (name "unconnected-(U8-V-Pad9)") (class "Default")
      (node (ref "U8") (pin "9") (pinfunction "V_9") (pintype "output+no_connect"))
    )
    (net (code "148") (name "unconnected-(U8-W{slash}PWM-Pad8)") (class "Default")
      (node (ref "U8") (pin "8") (pinfunction "W/PWM_8") (pintype "output+no_connect"))
    )
  )
)
